# arduino-uno.net
KiCad netlist of a schematic drawn in Altium Designer
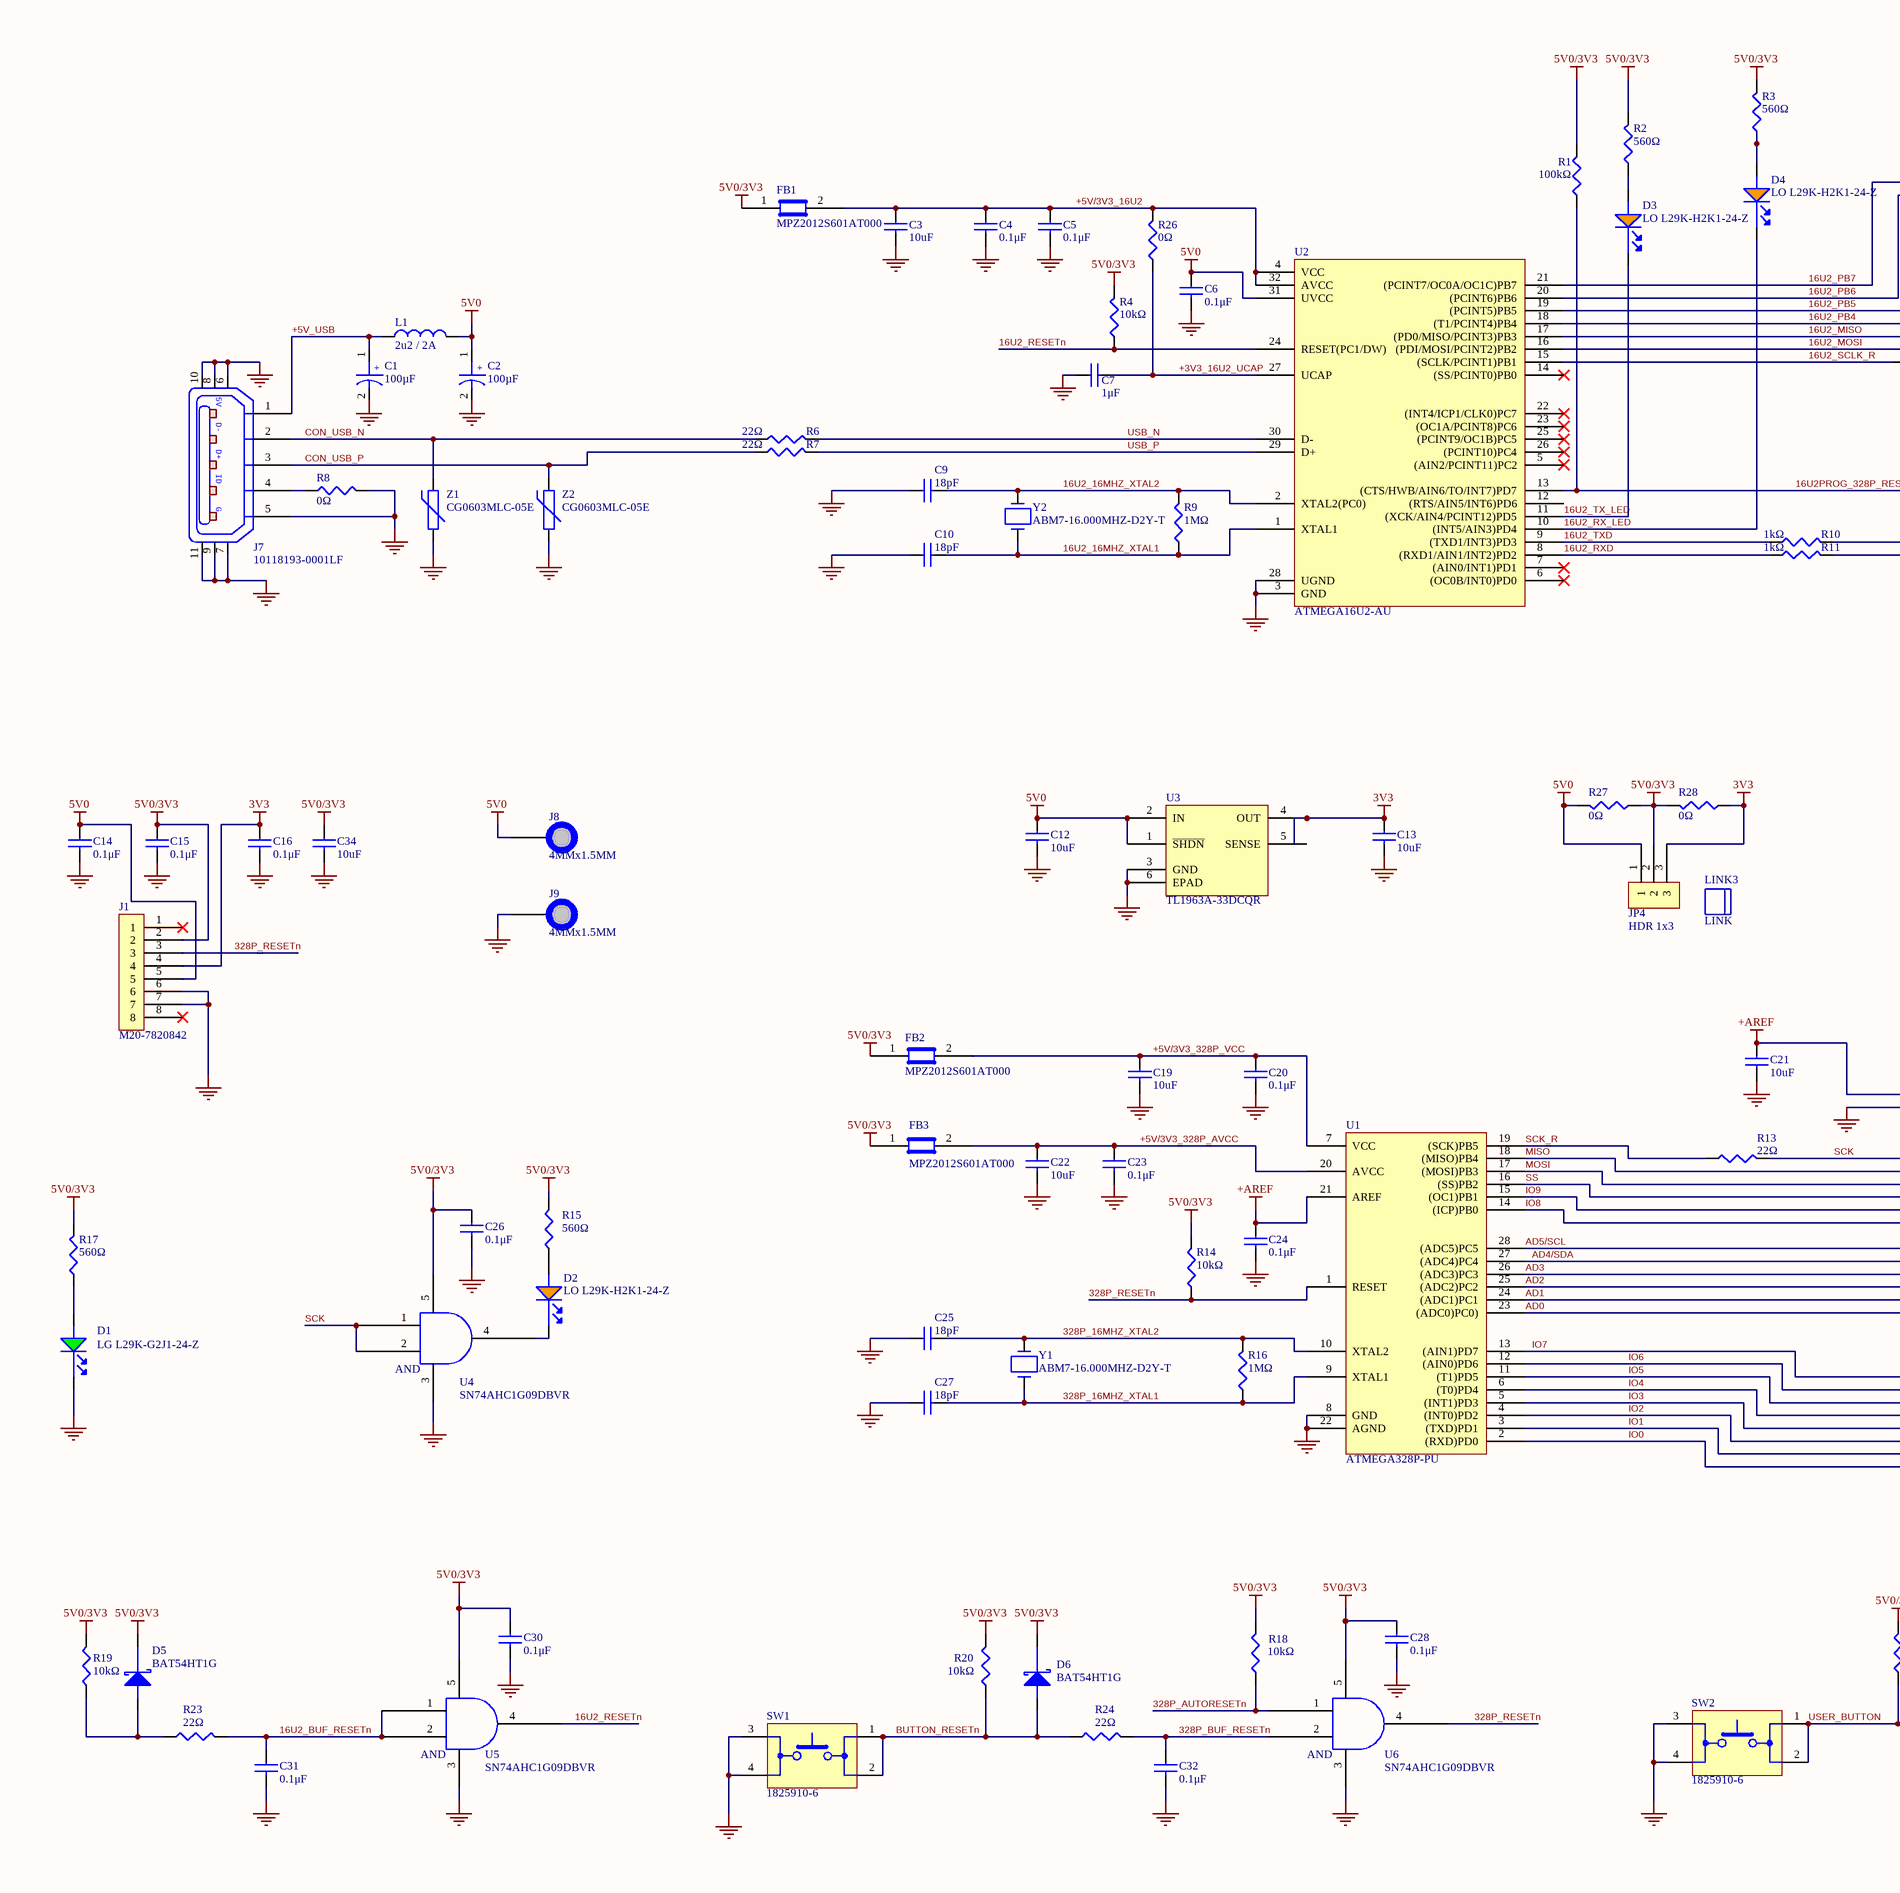
[diagram p0: arduino-uno.SchDoc, left]
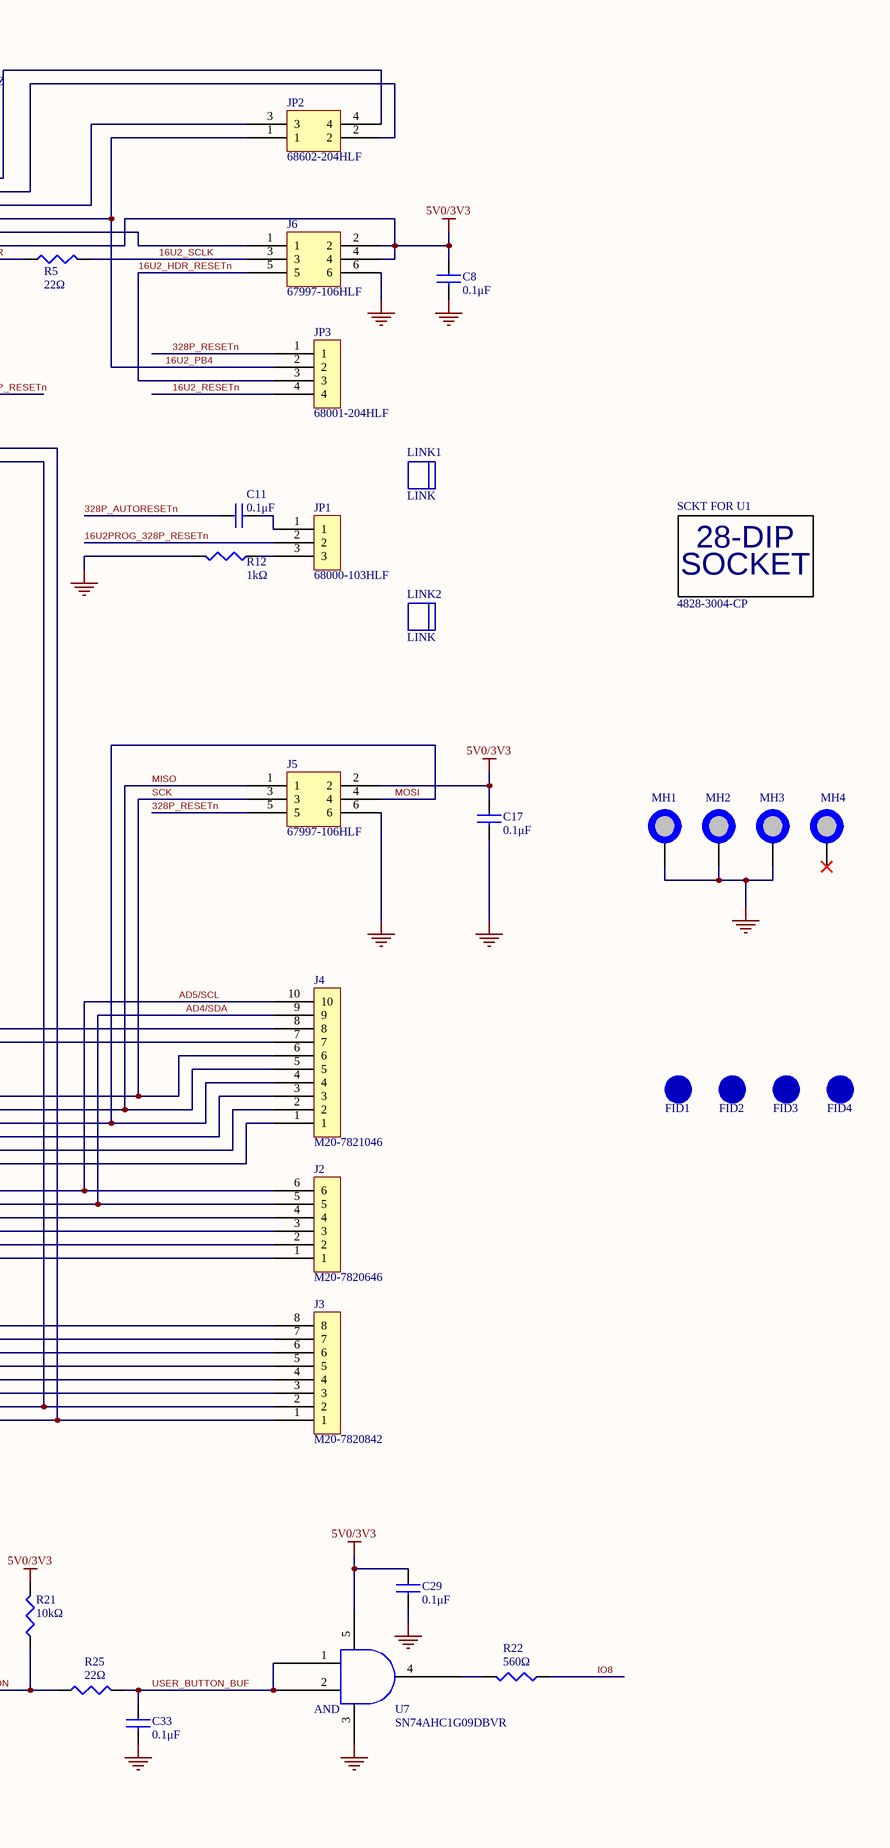
[diagram p1: arduino-uno.SchDoc, right]

(export (version "E")
  (design (tool "Eeschema 10.0.6"))
  (components
    (comp (ref "C1")
      (value "100µF")
      (footprint "C_ALU_C_SIZE")
      (description "CAP ALUM 100UF 10V 20% SMD")
      (fields
        (field (name "MANUFACTURER") "Panasonic Electronic Components")
        (field (name "MANUFACTURER PART NUMBER") "EEE-1AA101WR")
        (field (name ".CREATOR") "MM")
        (field (name ".CHECKED PCB") "RF")
        (field (name ".CHECKED SCH") "RF")
      )
      (libsource (lib "28Pins_Project_V1I1_PCB") (part "EEE-1AA101WR"))
    )
    (comp (ref "C2")
      (value "100µF")
      (footprint "C_ALU_C_SIZE")
      (description "CAP ALUM 100UF 10V 20% SMD")
      (fields
        (field (name "MANUFACTURER") "Panasonic Electronic Components")
        (field (name "MANUFACTURER PART NUMBER") "EEE-1AA101WR")
        (field (name ".CREATOR") "MM")
        (field (name ".CHECKED PCB") "RF")
        (field (name ".CHECKED SCH") "RF")
      )
      (libsource (lib "28Pins_Project_V1I1_PCB") (part "EEE-1AA101WR"))
    )
    (comp (ref "C3")
      (value "10uF")
      (footprint "C0805")
      (description "CAP CER 10UF 16V 20% X5R 0805")
      (fields
        (field (name "MANUFACTURER") "TDK Corporation")
        (field (name "MANUFACTURER PART NUMBER") "C2012X5R1C106M/1.25")
      )
      (libsource (lib "28Pins_Project_V1I1_PCB") (part "C2012X5R1C106M"))
    )
    (comp (ref "C4")
      (value "0.1μF")
      (footprint "C0805")
      (description "CAP CER 0.1UF 50V 10% X7R 0805")
      (fields
        (field (name "MANUFACTURER") "TDK Corporation")
        (field (name "MANUFACTURER PART NUMBER") "C2012X7R1H104K085AA")
        (field (name ".CREATOR") "MM")
        (field (name ".CHECKED PCB") "RF")
        (field (name ".CHECKED SCH") "RF")
      )
      (libsource (lib "28Pins_Project_V1I1_PCB") (part "C2012X7R1H104K085AA"))
    )
    (comp (ref "C5")
      (value "0.1μF")
      (footprint "C0805")
      (description "CAP CER 0.1UF 50V 10% X7R 0805")
      (fields
        (field (name "MANUFACTURER") "TDK Corporation")
        (field (name "MANUFACTURER PART NUMBER") "C2012X7R1H104K085AA")
        (field (name ".CREATOR") "MM")
        (field (name ".CHECKED PCB") "RF")
        (field (name ".CHECKED SCH") "RF")
      )
      (libsource (lib "28Pins_Project_V1I1_PCB") (part "C2012X7R1H104K085AA"))
    )
    (comp (ref "C6")
      (value "0.1μF")
      (footprint "C0805")
      (description "CAP CER 0.1UF 50V 10% X7R 0805")
      (fields
        (field (name "MANUFACTURER") "TDK Corporation")
        (field (name "MANUFACTURER PART NUMBER") "C2012X7R1H104K085AA")
        (field (name ".CREATOR") "MM")
        (field (name ".CHECKED PCB") "RF")
        (field (name ".CHECKED SCH") "RF")
      )
      (libsource (lib "28Pins_Project_V1I1_PCB") (part "C2012X7R1H104K085AA"))
    )
    (comp (ref "C7")
      (value "1μF")
      (footprint "C0805")
      (description "CAP CER 1UF 25V 10% X5R 0805")
      (fields
        (field (name "MANUFACTURER") "TDK Corporation")
        (field (name "MANUFACTURER PART NUMBER") "C2012X5R1E105K125AA")
        (field (name ".CREATOR") "MM")
        (field (name ".CHECKED PCB") "RF")
        (field (name ".CHECKED SCH") "RF")
      )
      (libsource (lib "28Pins_Project_V1I1_PCB") (part "C2012X5R1E105K125AA"))
    )
    (comp (ref "C8")
      (value "0.1μF")
      (footprint "C0805")
      (description "CAP CER 0.1UF 50V 10% X7R 0805")
      (fields
        (field (name "MANUFACTURER") "TDK Corporation")
        (field (name "MANUFACTURER PART NUMBER") "C2012X7R1H104K085AA")
        (field (name ".CREATOR") "MM")
        (field (name ".CHECKED PCB") "RF")
        (field (name ".CHECKED SCH") "RF")
      )
      (libsource (lib "28Pins_Project_V1I1_PCB") (part "C2012X7R1H104K085AA"))
    )
    (comp (ref "C9")
      (value "18pF")
      (footprint "C0805")
      (description "CAP CER 18PF 50V 5% NP0 0805")
      (fields
        (field (name "MANUFACTURER") "Kemet")
        (field (name "MANUFACTURER PART NUMBER") "C0805C180J5GACTU")
        (field (name ".CREATOR") "MM")
        (field (name ".CHECKED PCB") "RF")
        (field (name ".CHECKED SCH") "RF")
      )
      (libsource (lib "28Pins_Project_V1I1_PCB") (part "C0805C180J5GACTU"))
    )
    (comp (ref "C10")
      (value "18pF")
      (footprint "C0805")
      (description "CAP CER 18PF 50V 5% NP0 0805")
      (fields
        (field (name "MANUFACTURER") "Kemet")
        (field (name "MANUFACTURER PART NUMBER") "C0805C180J5GACTU")
        (field (name ".CREATOR") "MM")
        (field (name ".CHECKED PCB") "RF")
        (field (name ".CHECKED SCH") "RF")
      )
      (libsource (lib "28Pins_Project_V1I1_PCB") (part "C0805C180J5GACTU"))
    )
    (comp (ref "C11")
      (value "0.1μF")
      (footprint "C0805")
      (description "CAP CER 0.1UF 50V 10% X7R 0805")
      (fields
        (field (name "MANUFACTURER") "TDK Corporation")
        (field (name "MANUFACTURER PART NUMBER") "C2012X7R1H104K085AA")
        (field (name ".CREATOR") "MM")
        (field (name ".CHECKED PCB") "RF")
        (field (name ".CHECKED SCH") "RF")
      )
      (libsource (lib "28Pins_Project_V1I1_PCB") (part "C2012X7R1H104K085AA"))
    )
    (comp (ref "C12")
      (value "10uF")
      (footprint "C0805")
      (description "CAP CER 10UF 16V 20% X5R 0805")
      (fields
        (field (name "MANUFACTURER") "TDK Corporation")
        (field (name "MANUFACTURER PART NUMBER") "C2012X5R1C106M/1.25")
      )
      (libsource (lib "28Pins_Project_V1I1_PCB") (part "C2012X5R1C106M"))
    )
    (comp (ref "C13")
      (value "10uF")
      (footprint "C0805")
      (description "CAP CER 10UF 16V 20% X5R 0805")
      (fields
        (field (name "MANUFACTURER") "TDK Corporation")
        (field (name "MANUFACTURER PART NUMBER") "C2012X5R1C106M/1.25")
      )
      (libsource (lib "28Pins_Project_V1I1_PCB") (part "C2012X5R1C106M"))
    )
    (comp (ref "C14")
      (value "0.1μF")
      (footprint "C0805")
      (description "CAP CER 0.1UF 50V 10% X7R 0805")
      (fields
        (field (name "MANUFACTURER") "TDK Corporation")
        (field (name "MANUFACTURER PART NUMBER") "C2012X7R1H104K085AA")
        (field (name ".CREATOR") "MM")
        (field (name ".CHECKED PCB") "RF")
        (field (name ".CHECKED SCH") "RF")
      )
      (libsource (lib "28Pins_Project_V1I1_PCB") (part "C2012X7R1H104K085AA"))
    )
    (comp (ref "C15")
      (value "0.1μF")
      (footprint "C0805")
      (description "CAP CER 0.1UF 50V 10% X7R 0805")
      (fields
        (field (name "MANUFACTURER") "TDK Corporation")
        (field (name "MANUFACTURER PART NUMBER") "C2012X7R1H104K085AA")
        (field (name ".CREATOR") "MM")
        (field (name ".CHECKED PCB") "RF")
        (field (name ".CHECKED SCH") "RF")
      )
      (libsource (lib "28Pins_Project_V1I1_PCB") (part "C2012X7R1H104K085AA"))
    )
    (comp (ref "C16")
      (value "0.1μF")
      (footprint "C0805")
      (description "CAP CER 0.1UF 50V 10% X7R 0805")
      (fields
        (field (name "MANUFACTURER") "TDK Corporation")
        (field (name "MANUFACTURER PART NUMBER") "C2012X7R1H104K085AA")
        (field (name ".CREATOR") "MM")
        (field (name ".CHECKED PCB") "RF")
        (field (name ".CHECKED SCH") "RF")
      )
      (libsource (lib "28Pins_Project_V1I1_PCB") (part "C2012X7R1H104K085AA"))
    )
    (comp (ref "C17")
      (value "0.1μF")
      (footprint "C0805")
      (description "CAP CER 0.1UF 50V 10% X7R 0805")
      (fields
        (field (name "MANUFACTURER") "TDK Corporation")
        (field (name "MANUFACTURER PART NUMBER") "C2012X7R1H104K085AA")
        (field (name ".CREATOR") "MM")
        (field (name ".CHECKED PCB") "RF")
        (field (name ".CHECKED SCH") "RF")
      )
      (libsource (lib "28Pins_Project_V1I1_PCB") (part "C2012X7R1H104K085AA"))
    )
    (comp (ref "C19")
      (value "10uF")
      (footprint "C0805")
      (description "CAP CER 10UF 16V 20% X5R 0805")
      (fields
        (field (name "MANUFACTURER") "TDK Corporation")
        (field (name "MANUFACTURER PART NUMBER") "C2012X5R1C106M/1.25")
      )
      (libsource (lib "28Pins_Project_V1I1_PCB") (part "C2012X5R1C106M"))
    )
    (comp (ref "C20")
      (value "0.1μF")
      (footprint "C0805")
      (description "CAP CER 0.1UF 50V 10% X7R 0805")
      (fields
        (field (name "MANUFACTURER") "TDK Corporation")
        (field (name "MANUFACTURER PART NUMBER") "C2012X7R1H104K085AA")
        (field (name ".CREATOR") "MM")
        (field (name ".CHECKED PCB") "RF")
        (field (name ".CHECKED SCH") "RF")
      )
      (libsource (lib "28Pins_Project_V1I1_PCB") (part "C2012X7R1H104K085AA"))
    )
    (comp (ref "C21")
      (value "10uF")
      (footprint "C0805")
      (description "CAP CER 10UF 16V 20% X5R 0805")
      (fields
        (field (name "MANUFACTURER") "TDK Corporation")
        (field (name "MANUFACTURER PART NUMBER") "C2012X5R1C106M/1.25")
      )
      (libsource (lib "28Pins_Project_V1I1_PCB") (part "C2012X5R1C106M"))
    )
    (comp (ref "C22")
      (value "10uF")
      (footprint "C0805")
      (description "CAP CER 10UF 16V 20% X5R 0805")
      (fields
        (field (name "MANUFACTURER") "TDK Corporation")
        (field (name "MANUFACTURER PART NUMBER") "C2012X5R1C106M/1.25")
      )
      (libsource (lib "28Pins_Project_V1I1_PCB") (part "C2012X5R1C106M"))
    )
    (comp (ref "C23")
      (value "0.1μF")
      (footprint "C0805")
      (description "CAP CER 0.1UF 50V 10% X7R 0805")
      (fields
        (field (name "MANUFACTURER") "TDK Corporation")
        (field (name "MANUFACTURER PART NUMBER") "C2012X7R1H104K085AA")
        (field (name ".CREATOR") "MM")
        (field (name ".CHECKED PCB") "RF")
        (field (name ".CHECKED SCH") "RF")
      )
      (libsource (lib "28Pins_Project_V1I1_PCB") (part "C2012X7R1H104K085AA"))
    )
    (comp (ref "C24")
      (value "0.1μF")
      (footprint "C0805")
      (description "CAP CER 0.1UF 50V 10% X7R 0805")
      (fields
        (field (name "MANUFACTURER") "TDK Corporation")
        (field (name "MANUFACTURER PART NUMBER") "C2012X7R1H104K085AA")
        (field (name ".CREATOR") "MM")
        (field (name ".CHECKED PCB") "RF")
        (field (name ".CHECKED SCH") "RF")
      )
      (libsource (lib "28Pins_Project_V1I1_PCB") (part "C2012X7R1H104K085AA"))
    )
    (comp (ref "C25")
      (value "18pF")
      (footprint "C0805")
      (description "CAP CER 18PF 50V 5% NP0 0805")
      (fields
        (field (name "MANUFACTURER") "Kemet")
        (field (name "MANUFACTURER PART NUMBER") "C0805C180J5GACTU")
        (field (name ".CREATOR") "MM")
        (field (name ".CHECKED PCB") "RF")
        (field (name ".CHECKED SCH") "RF")
      )
      (libsource (lib "28Pins_Project_V1I1_PCB") (part "C0805C180J5GACTU"))
    )
    (comp (ref "C26")
      (value "0.1μF")
      (footprint "C0805")
      (description "CAP CER 0.1UF 50V 10% X7R 0805")
      (fields
        (field (name "MANUFACTURER") "TDK Corporation")
        (field (name "MANUFACTURER PART NUMBER") "C2012X7R1H104K085AA")
        (field (name ".CREATOR") "MM")
        (field (name ".CHECKED PCB") "RF")
        (field (name ".CHECKED SCH") "RF")
      )
      (libsource (lib "28Pins_Project_V1I1_PCB") (part "C2012X7R1H104K085AA"))
    )
    (comp (ref "C27")
      (value "18pF")
      (footprint "C0805")
      (description "CAP CER 18PF 50V 5% NP0 0805")
      (fields
        (field (name "MANUFACTURER") "Kemet")
        (field (name "MANUFACTURER PART NUMBER") "C0805C180J5GACTU")
        (field (name ".CREATOR") "MM")
        (field (name ".CHECKED PCB") "RF")
        (field (name ".CHECKED SCH") "RF")
      )
      (libsource (lib "28Pins_Project_V1I1_PCB") (part "C0805C180J5GACTU"))
    )
    (comp (ref "C28")
      (value "0.1μF")
      (footprint "C0805")
      (description "CAP CER 0.1UF 50V 10% X7R 0805")
      (fields
        (field (name "MANUFACTURER") "TDK Corporation")
        (field (name "MANUFACTURER PART NUMBER") "C2012X7R1H104K085AA")
        (field (name ".CREATOR") "MM")
        (field (name ".CHECKED PCB") "RF")
        (field (name ".CHECKED SCH") "RF")
      )
      (libsource (lib "28Pins_Project_V1I1_PCB") (part "C2012X7R1H104K085AA"))
    )
    (comp (ref "C29")
      (value "0.1μF")
      (footprint "C0805")
      (description "CAP CER 0.1UF 50V 10% X7R 0805")
      (fields
        (field (name "MANUFACTURER") "TDK Corporation")
        (field (name "MANUFACTURER PART NUMBER") "C2012X7R1H104K085AA")
        (field (name ".CREATOR") "MM")
        (field (name ".CHECKED PCB") "RF")
        (field (name ".CHECKED SCH") "RF")
      )
      (libsource (lib "28Pins_Project_V1I1_PCB") (part "C2012X7R1H104K085AA"))
    )
    (comp (ref "C30")
      (value "0.1μF")
      (footprint "C0805")
      (description "CAP CER 0.1UF 50V 10% X7R 0805")
      (fields
        (field (name "MANUFACTURER") "TDK Corporation")
        (field (name "MANUFACTURER PART NUMBER") "C2012X7R1H104K085AA")
        (field (name ".CREATOR") "MM")
        (field (name ".CHECKED PCB") "RF")
        (field (name ".CHECKED SCH") "RF")
      )
      (libsource (lib "28Pins_Project_V1I1_PCB") (part "C2012X7R1H104K085AA"))
    )
    (comp (ref "C31")
      (value "0.1μF")
      (footprint "C0805")
      (description "CAP CER 0.1UF 50V 10% X7R 0805")
      (fields
        (field (name "MANUFACTURER") "TDK Corporation")
        (field (name "MANUFACTURER PART NUMBER") "C2012X7R1H104K085AA")
        (field (name ".CREATOR") "MM")
        (field (name ".CHECKED PCB") "RF")
        (field (name ".CHECKED SCH") "RF")
      )
      (libsource (lib "28Pins_Project_V1I1_PCB") (part "C2012X7R1H104K085AA"))
    )
    (comp (ref "C32")
      (value "0.1μF")
      (footprint "C0805")
      (description "CAP CER 0.1UF 50V 10% X7R 0805")
      (fields
        (field (name "MANUFACTURER") "TDK Corporation")
        (field (name "MANUFACTURER PART NUMBER") "C2012X7R1H104K085AA")
        (field (name ".CREATOR") "MM")
        (field (name ".CHECKED PCB") "RF")
        (field (name ".CHECKED SCH") "RF")
      )
      (libsource (lib "28Pins_Project_V1I1_PCB") (part "C2012X7R1H104K085AA"))
    )
    (comp (ref "C33")
      (value "0.1μF")
      (footprint "C0805")
      (description "CAP CER 0.1UF 50V 10% X7R 0805")
      (fields
        (field (name "MANUFACTURER") "TDK Corporation")
        (field (name "MANUFACTURER PART NUMBER") "C2012X7R1H104K085AA")
        (field (name ".CREATOR") "MM")
        (field (name ".CHECKED PCB") "RF")
        (field (name ".CHECKED SCH") "RF")
      )
      (libsource (lib "28Pins_Project_V1I1_PCB") (part "C2012X7R1H104K085AA"))
    )
    (comp (ref "C34")
      (value "10uF")
      (footprint "C0805")
      (description "CAP CER 10UF 16V 20% X5R 0805")
      (fields
        (field (name "MANUFACTURER") "TDK Corporation")
        (field (name "MANUFACTURER PART NUMBER") "C2012X5R1C106M/1.25")
      )
      (libsource (lib "28Pins_Project_V1I1_PCB") (part "C2012X5R1C106M"))
    )
    (comp (ref "D1")
      (value "LG L29K-G2J1-24-Z")
      (footprint "LED_0603")
      (description "LED SMARTLED GREEN 570NM 0603")
      (fields (field (name "MANUFACTURER") "OSRAM Opto Semiconductors Inc"))
      (libsource (lib "28Pins_Project_V1I1_PCB") (part "LG L29K-G2J1-24-Z"))
    )
    (comp (ref "D2")
      (value "LO L29K-H2K1-24-Z")
      (footprint "LED_0603")
      (description "LED SMARTLED ORANGE 606NM 0603")
      (fields (field (name "MANUFACTURER") "OSRAM Opto Semiconductors Inc"))
      (libsource (lib "28Pins_Project_V1I1_PCB") (part "LO L29K-H2K1-24-Z"))
    )
    (comp (ref "D3")
      (value "LO L29K-H2K1-24-Z")
      (footprint "LED_0603")
      (description "LED SMARTLED ORANGE 606NM 0603")
      (fields (field (name "MANUFACTURER") "OSRAM Opto Semiconductors Inc"))
      (libsource (lib "28Pins_Project_V1I1_PCB") (part "LO L29K-H2K1-24-Z"))
    )
    (comp (ref "D4")
      (value "LO L29K-H2K1-24-Z")
      (footprint "LED_0603")
      (description "LED SMARTLED ORANGE 606NM 0603")
      (fields (field (name "MANUFACTURER") "OSRAM Opto Semiconductors Inc"))
      (libsource (lib "28Pins_Project_V1I1_PCB") (part "LO L29K-H2K1-24-Z"))
    )
    (comp (ref "D5")
      (value "BAT54HT1G")
      (footprint "SOD323")
      (description "DIODE SCHOTTKY 30V 0.2A SOD323")
      (fields (field (name "MANUFACTURER") "Fairchild Semiconductor") (field (name ".CREATOR") "MM"))
      (libsource (lib "28Pins_Project_V1I1_PCB") (part "BAT54HT1G"))
    )
    (comp (ref "D6")
      (value "BAT54HT1G")
      (footprint "SOD323")
      (description "DIODE SCHOTTKY 30V 0.2A SOD323")
      (fields (field (name "MANUFACTURER") "Fairchild Semiconductor") (field (name ".CREATOR") "MM"))
      (libsource (lib "28Pins_Project_V1I1_PCB") (part "BAT54HT1G"))
    )
    (comp (ref "FB1")
      (value "MPZ2012S601AT000")
      (footprint "C0805")
      (description "FERRITE CHIP BEAD 600 OHM SMD")
      (fields
        (field (name "MANUFACTURER") "TDK Corporation")
        (field (name ".CREATOR") "MM")
        (field (name ".CHECKED PCB") "RF")
        (field (name ".CHECKED SCH") "RF")
      )
      (libsource (lib "28Pins_Project_V1I1_PCB") (part "MPZ2012S601AT000"))
    )
    (comp (ref "FB2")
      (value "MPZ2012S601AT000")
      (footprint "C0805")
      (description "FERRITE CHIP BEAD 600 OHM SMD")
      (fields
        (field (name "MANUFACTURER") "TDK Corporation")
        (field (name ".CREATOR") "MM")
        (field (name ".CHECKED PCB") "RF")
        (field (name ".CHECKED SCH") "RF")
      )
      (libsource (lib "28Pins_Project_V1I1_PCB") (part "MPZ2012S601AT000"))
    )
    (comp (ref "FB3")
      (value "MPZ2012S601AT000")
      (footprint "C0805")
      (description "FERRITE CHIP BEAD 600 OHM SMD")
      (fields
        (field (name "MANUFACTURER") "TDK Corporation")
        (field (name ".CREATOR") "MM")
        (field (name ".CHECKED PCB") "RF")
        (field (name ".CHECKED SCH") "RF")
      )
      (libsource (lib "28Pins_Project_V1I1_PCB") (part "MPZ2012S601AT000"))
    )
    (comp (ref "FID1")
      (value "FID_1MMC")
      (footprint "FID_40X120D")
      (description "Fiducial 40mil Diameter, 120mil Mask")
      (libsource (lib "28Pins_Project_V1I1_PCB") (part "FID_1MMC"))
    )
    (comp (ref "FID2")
      (value "FID_1MMC")
      (footprint "FID_40X120D")
      (description "Fiducial 40mil Diameter, 120mil Mask")
      (libsource (lib "28Pins_Project_V1I1_PCB") (part "FID_1MMC"))
    )
    (comp (ref "FID3")
      (value "FID_1MMC")
      (footprint "FID_40X120D")
      (description "Fiducial 40mil Diameter, 120mil Mask")
      (libsource (lib "28Pins_Project_V1I1_PCB") (part "FID_1MMC"))
    )
    (comp (ref "FID4")
      (value "FID_1MMC")
      (footprint "FID_40X120D")
      (description "Fiducial 40mil Diameter, 120mil Mask")
      (libsource (lib "28Pins_Project_V1I1_PCB") (part "FID_1MMC"))
    )
    (comp (ref "J1")
      (value "M20-7820842")
      (footprint "Hdr_Female_1x8_2.54mm")
      (description "08-WAY SIL VERT SOCKET L/FREE")
      (fields
        (field (name "MANUFACTURER") "Harwin Inc")
        (field (name ".CREATOR") "MM")
        (field (name ".CHECKED PCB") "RF")
        (field (name ".CHECKED SCH") "RF")
      )
      (libsource (lib "") (part "M20-7820842_1"))
    )
    (comp (ref "J2")
      (value "M20-7820646")
      (footprint "Hdr_Female_1x6_2.54mm")
      (description "06-WAY SIL VERT SOCKET L/FREE")
      (fields
        (field (name "MANUFACTURER") "Harwin Inc")
        (field (name ".CHECKED PCB") "MM")
        (field (name ".CHECKED SCH") "MM")
        (field (name ".CREATOR") "MM")
      )
      (libsource (lib "28Pins_Project_V1I1_PCB") (part "M20-7820646"))
    )
    (comp (ref "J3")
      (value "M20-7820842")
      (footprint "Hdr_Female_1x8_2.54mm")
      (description "08-WAY SIL VERT SOCKET L/FREE")
      (fields
        (field (name "MANUFACTURER") "Harwin Inc")
        (field (name ".CREATOR") "MM")
        (field (name ".CHECKED PCB") "RF")
        (field (name ".CHECKED SCH") "RF")
      )
      (libsource (lib "28Pins_Project_V1I1_PCB") (part "M20-7820842"))
    )
    (comp (ref "J4")
      (value "M20-7821046")
      (footprint "Hdr_Female_1x10_2.54mm")
      (description "10-WAY SIL VERT SOCKET L/FREE")
      (fields
        (field (name "MANUFACTURER") "Harwin Inc")
        (field (name ".CREATOR") "MM")
        (field (name ".CHECKED PCB") "RF")
        (field (name ".CHECKED SCH") "RF")
      )
      (libsource (lib "28Pins_Project_V1I1_PCB") (part "M20-7821046"))
    )
    (comp (ref "J5")
      (value "67997-106HLF")
      (footprint "HDR_2x3_2.54MM")
      (description "CONN HEADER 6POS .100 STR 30AU")
      (fields
        (field (name "MANUFACTURER") "FCI")
        (field (name ".CREATOR") "MM")
        (field (name ".CHECKED PCB") "RF")
        (field (name ".CHECKED SCH") "RF")
      )
      (libsource (lib "28Pins_Project_V1I1_PCB") (part "67997-106HLF"))
    )
    (comp (ref "J6")
      (value "67997-106HLF")
      (footprint "HDR_2x3_2.54MM")
      (description "CONN HEADER 6POS .100 STR 30AU")
      (fields
        (field (name "MANUFACTURER") "FCI")
        (field (name ".CREATOR") "MM")
        (field (name ".CHECKED PCB") "RF")
        (field (name ".CHECKED SCH") "RF")
      )
      (libsource (lib "28Pins_Project_V1I1_PCB") (part "67997-106HLF"))
    )
    (comp (ref "J7")
      (value "10118193-0001LF")
      (footprint "10118193")
      (description "CONN USB MICRO B RECPT SMT R/A")
      (fields
        (field (name "MANUFACTURER") "FCI")
        (field (name ".CREATOR") "MM")
        (field (name ".CHECKED PCB") "RF")
        (field (name ".CHECKED SCH") "MM")
      )
      (libsource (lib "28Pins_Project_V1I1_PCB") (part "10118193-0001LF"))
    )
    (comp (ref "J8")
      (value "4MMx1.5MM")
      (footprint "PAD_WITH_HOLE_4MMx1.5MM")
      (description "Pad with a hole 4mm x 1.5mm")
      (libsource (lib "28Pins_Project_V1I1_PCB") (part "PAD_WITH_HOLE_4MMx1.5MM"))
    )
    (comp (ref "J9")
      (value "4MMx1.5MM")
      (footprint "PAD_WITH_HOLE_4MMx1.5MM")
      (description "Pad with a hole 4mm x 1.5mm")
      (libsource (lib "28Pins_Project_V1I1_PCB") (part "PAD_WITH_HOLE_4MMx1.5MM"))
    )
    (comp (ref "JP1")
      (value "68000-103HLF")
      (footprint "Hdr_1x3_2.54mm")
      (description "BERGSTIK II .100\" SR STRAIGHT")
      (fields (field (name "MANUFACTURER") "FCI") (field (name ".CREATOR") "MM"))
      (libsource (lib "") (part "68000-103HLF_1"))
    )
    (comp (ref "JP2")
      (value "68602-204HLF")
      (footprint "HDR_2x2_2.54MM")
      (description "CONN HEADER 4POS .100 STR 15AU")
      (fields
        (field (name "MANUFACTURER") "FCI")
        (field (name ".CREATOR") "MM")
        (field (name ".CHECKED PCB") "RF")
        (field (name ".CHECKED SCH") "RF")
      )
      (libsource (lib "28Pins_Project_V1I1_PCB") (part "68602-204HLF"))
    )
    (comp (ref "JP3")
      (value "68001-204HLF")
      (footprint "HDR_1x4_2.54MM")
      (description "CONN HEADER 4POS .100 STR 15AU")
      (fields
        (field (name "MANUFACTURER") "FCI")
        (field (name ".CHECKED PCB") "RF")
        (field (name ".CHECKED SCH") "RF")
      )
      (libsource (lib "28Pins_Project_V1I1_PCB") (part "68001-204HLF"))
    )
    (comp (ref "JP4")
      (value "HDR 1x3")
      (footprint "Hdr_1x3_2.54mm")
      (description "BERGSTIK II .100\" SR STRAIGHT")
      (fields
        (field (name "MANUFACTURER") "FCI")
        (field (name "MANUFACTURER PART NUMBER") "68000-103HLF")
        (field (name ".CREATOR") "MM")
      )
      (libsource (lib "28Pins_Project_V1I1_PCB") (part "68000-103HLF"))
    )
    (comp (ref "L1")
      (value "2u2 / 2A")
      (footprint "C1210_IND")
      (description "FIXED IND 2.2UH 2A 80 MOHM SMD")
      (fields
        (field (name "MANUFACTURER") "Kemet")
        (field (name "MANUFACTURER PART NUMBER") "L1210R2R2MDWIT")
        (field (name ".CREATOR") "MM")
        (field (name ".CHECKED PCB") "RF")
        (field (name ".CHECKED SCH") "RF")
      )
      (libsource (lib "28Pins_Project_V1I1_PCB") (part "L1210R2R2MDWIT"))
    )
    (comp (ref "LINK1")
      (value "LINK")
      (description "CONN JUMPER SHORTING .100\" GOLD")
      (fields
        (field (name "MANUFACTURER") "Sullins Connector Solutions")
        (field (name "MANUFACTURER PART NUMBER") "QPC02SXGN-RC")
      )
      (libsource (lib "28Pins_Project_V1I1_PCB") (part "QPC02SXGN-RC"))
    )
    (comp (ref "LINK2")
      (value "LINK")
      (description "CONN JUMPER SHORTING .100\" GOLD")
      (fields
        (field (name "MANUFACTURER") "Sullins Connector Solutions")
        (field (name "MANUFACTURER PART NUMBER") "QPC02SXGN-RC")
      )
      (libsource (lib "28Pins_Project_V1I1_PCB") (part "QPC02SXGN-RC"))
    )
    (comp (ref "LINK3")
      (value "LINK")
      (description "CONN JUMPER SHORTING .100\" GOLD")
      (fields
        (field (name "MANUFACTURER") "Sullins Connector Solutions")
        (field (name "MANUFACTURER PART NUMBER") "QPC02SXGN-RC")
      )
      (libsource (lib "28Pins_Project_V1I1_PCB") (part "QPC02SXGN-RC"))
    )
    (comp (ref "MH1")
      (value "MH_7.4MMC_3.2MMD")
      (footprint "MH_7.4MMD_3.2MMD")
      (description "Mounting Hole 7.4mm Diameter, 3.2mm Drill")
      (fields (field (name ".CREATOR") "MM"))
      (libsource (lib "28Pins_Project_V1I1_PCB") (part "MH_7.4MMC_3.2MMD"))
    )
    (comp (ref "MH2")
      (value "MH_7.4MMC_3.2MMD")
      (footprint "MH_7.4MMD_3.2MMD")
      (description "Mounting Hole 7.4mm Diameter, 3.2mm Drill")
      (fields (field (name ".CREATOR") "MM"))
      (libsource (lib "28Pins_Project_V1I1_PCB") (part "MH_7.4MMC_3.2MMD"))
    )
    (comp (ref "MH3")
      (value "MH_7.4MMC_3.2MMD")
      (footprint "MH_7.4MMD_3.2MMD")
      (description "Mounting Hole 7.4mm Diameter, 3.2mm Drill")
      (fields (field (name ".CREATOR") "MM"))
      (libsource (lib "28Pins_Project_V1I1_PCB") (part "MH_7.4MMC_3.2MMD"))
    )
    (comp (ref "MH4")
      (value "MH_7.4MMNC_3.2MMD")
      (footprint "MH_7.4MMD_3.2MMD_NON_COPPER_NPTH")
      (description "Mounting Hole 7.4mm Diameter (Non Copper), 3.2mm Drill NPTH")
      (libsource (lib "28Pins_Project_V1I1_PCB") (part "MH_7.4MMNC_3.2MMD"))
    )
    (comp (ref "R1")
      (value "100kΩ")
      (footprint "R0805")
      (description "RES SMD 100K OHM 1% 1/8W 0805")
      (fields
        (field (name "MANUFACTURER") "Yageo")
        (field (name "MANUFACTURER PART NUMBER") "RC0805FR-07100KL")
        (field (name ".CREATOR") "MM")
        (field (name ".CHECKED PCB") "RF")
        (field (name ".CHECKED SCH") "RF")
      )
      (libsource (lib "28Pins_Project_V1I1_PCB") (part "RC0805FR-07100KL"))
    )
    (comp (ref "R2")
      (value "560Ω")
      (footprint "R0805")
      (description "RES SMD 560 OHM 1% 1/8W 0805")
      (fields
        (field (name "MANUFACTURER") "Yageo")
        (field (name "MANUFACTURER PART NUMBER") "RC0805FR-07560RL")
        (field (name ".CREATOR") "MM")
        (field (name ".CHECKED PCB") "RF")
        (field (name ".CHECKED SCH") "RF")
      )
      (libsource (lib "28Pins_Project_V1I1_PCB") (part "RC0805FR-07560RL"))
    )
    (comp (ref "R3")
      (value "560Ω")
      (footprint "R0805")
      (description "RES SMD 560 OHM 1% 1/8W 0805")
      (fields
        (field (name "MANUFACTURER") "Yageo")
        (field (name "MANUFACTURER PART NUMBER") "RC0805FR-07560RL")
        (field (name ".CREATOR") "MM")
        (field (name ".CHECKED PCB") "RF")
        (field (name ".CHECKED SCH") "RF")
      )
      (libsource (lib "28Pins_Project_V1I1_PCB") (part "RC0805FR-07560RL"))
    )
    (comp (ref "R4")
      (value "10kΩ")
      (footprint "R0805")
      (description "RES SMD 10K OHM 1% 1/8W 0805")
      (fields
        (field (name "MANUFACTURER") "Yageo")
        (field (name "MANUFACTURER PART NUMBER") "RC0805FR-0710KL")
        (field (name ".CREATOR") "MM")
        (field (name ".CHECKED PCB") "RF")
        (field (name ".CHECKED SCH") "RF")
      )
      (libsource (lib "28Pins_Project_V1I1_PCB") (part "RC0805FR-0710KL"))
    )
    (comp (ref "R5")
      (value "22Ω")
      (footprint "R0805")
      (description "RES SMD 22 OHM 1% 1/8W 0805")
      (fields
        (field (name "MANUFACTURER") "Yageo")
        (field (name "MANUFACTURER PART NUMBER") "RC0805FR-0722RL")
        (field (name ".CREATOR") "MM")
        (field (name ".CHECKED PCB") "RF")
        (field (name ".CHECKED SCH") "RF")
      )
      (libsource (lib "28Pins_Project_V1I1_PCB") (part "RC0805FR-0722RL"))
    )
    (comp (ref "R6")
      (value "22Ω")
      (footprint "R0805")
      (description "RES SMD 22 OHM 1% 1/8W 0805")
      (fields
        (field (name "MANUFACTURER") "Yageo")
        (field (name "MANUFACTURER PART NUMBER") "RC0805FR-0722RL")
        (field (name ".CREATOR") "MM")
        (field (name ".CHECKED PCB") "RF")
        (field (name ".CHECKED SCH") "RF")
      )
      (libsource (lib "28Pins_Project_V1I1_PCB") (part "RC0805FR-0722RL"))
    )
    (comp (ref "R7")
      (value "22Ω")
      (footprint "R0805")
      (description "RES SMD 22 OHM 1% 1/8W 0805")
      (fields
        (field (name "MANUFACTURER") "Yageo")
        (field (name "MANUFACTURER PART NUMBER") "RC0805FR-0722RL")
        (field (name ".CREATOR") "MM")
        (field (name ".CHECKED PCB") "RF")
        (field (name ".CHECKED SCH") "RF")
      )
      (libsource (lib "28Pins_Project_V1I1_PCB") (part "RC0805FR-0722RL"))
    )
    (comp (ref "R8")
      (value "0Ω")
      (footprint "R0805")
      (description "RES 0.0 OHM 1/8W 0805 SMD")
      (fields
        (field (name "MANUFACTURER") "Yageo")
        (field (name "MANUFACTURER PART NUMBER") "RC0805JR-070RL")
        (field (name ".CHECKED PCB") "RF")
        (field (name ".CHECKED SCH") "RF")
      )
      (libsource (lib "28Pins_Project_V1I1_PCB") (part "RC0805JR-070RL"))
    )
    (comp (ref "R9")
      (value "1MΩ")
      (footprint "R0805")
      (description "RES SMD 1M OHM 1% 1/8W 0805")
      (fields
        (field (name "MANUFACTURER") "Yageo")
        (field (name "MANUFACTURER PART NUMBER") "RC0805FR-071ML")
        (field (name ".CREATOR") "MM")
        (field (name ".CHECKED PCB") "RF")
        (field (name ".CHECKED SCH") "RF")
      )
      (libsource (lib "28Pins_Project_V1I1_PCB") (part "RC0805FR-071ML"))
    )
    (comp (ref "R10")
      (value "1kΩ")
      (footprint "R0805")
      (description "RES SMD 1K OHM 1% 1/8W 0805")
      (fields
        (field (name "MANUFACTURER") "Yageo")
        (field (name "MANUFACTURER PART NUMBER") "RC0805FR-071KL")
        (field (name ".CREATOR") "MM")
        (field (name ".CHECKED PCB") "RF")
        (field (name ".CHECKED SCH") "RF")
      )
      (libsource (lib "28Pins_Project_V1I1_PCB") (part "RC0805FR-071KL"))
    )
    (comp (ref "R11")
      (value "1kΩ")
      (footprint "R0805")
      (description "RES SMD 1K OHM 1% 1/8W 0805")
      (fields
        (field (name "MANUFACTURER") "Yageo")
        (field (name "MANUFACTURER PART NUMBER") "RC0805FR-071KL")
        (field (name ".CREATOR") "MM")
        (field (name ".CHECKED PCB") "RF")
        (field (name ".CHECKED SCH") "RF")
      )
      (libsource (lib "28Pins_Project_V1I1_PCB") (part "RC0805FR-071KL"))
    )
    (comp (ref "R12")
      (value "1kΩ")
      (footprint "R0805")
      (description "RES SMD 1K OHM 1% 1/8W 0805")
      (fields
        (field (name "MANUFACTURER") "Yageo")
        (field (name "MANUFACTURER PART NUMBER") "RC0805FR-071KL")
        (field (name ".CREATOR") "MM")
        (field (name ".CHECKED PCB") "RF")
        (field (name ".CHECKED SCH") "RF")
      )
      (libsource (lib "28Pins_Project_V1I1_PCB") (part "RC0805FR-071KL"))
    )
    (comp (ref "R13")
      (value "22Ω")
      (footprint "R0805")
      (description "RES SMD 22 OHM 1% 1/8W 0805")
      (fields
        (field (name "MANUFACTURER") "Yageo")
        (field (name "MANUFACTURER PART NUMBER") "RC0805FR-0722RL")
        (field (name ".CREATOR") "MM")
        (field (name ".CHECKED PCB") "RF")
        (field (name ".CHECKED SCH") "RF")
      )
      (libsource (lib "28Pins_Project_V1I1_PCB") (part "RC0805FR-0722RL"))
    )
    (comp (ref "R14")
      (value "10kΩ")
      (footprint "R0805")
      (description "RES SMD 10K OHM 1% 1/8W 0805")
      (fields
        (field (name "MANUFACTURER") "Yageo")
        (field (name "MANUFACTURER PART NUMBER") "RC0805FR-0710KL")
        (field (name ".CREATOR") "MM")
        (field (name ".CHECKED PCB") "RF")
        (field (name ".CHECKED SCH") "RF")
      )
      (libsource (lib "28Pins_Project_V1I1_PCB") (part "RC0805FR-0710KL"))
    )
    (comp (ref "R15")
      (value "560Ω")
      (footprint "R0805")
      (description "RES SMD 560 OHM 1% 1/8W 0805")
      (fields
        (field (name "MANUFACTURER") "Yageo")
        (field (name "MANUFACTURER PART NUMBER") "RC0805FR-07560RL")
        (field (name ".CREATOR") "MM")
        (field (name ".CHECKED PCB") "RF")
        (field (name ".CHECKED SCH") "RF")
      )
      (libsource (lib "28Pins_Project_V1I1_PCB") (part "RC0805FR-07560RL"))
    )
    (comp (ref "R16")
      (value "1MΩ")
      (footprint "R0805")
      (description "RES SMD 1M OHM 1% 1/8W 0805")
      (fields
        (field (name "MANUFACTURER") "Yageo")
        (field (name "MANUFACTURER PART NUMBER") "RC0805FR-071ML")
        (field (name ".CREATOR") "MM")
        (field (name ".CHECKED PCB") "RF")
        (field (name ".CHECKED SCH") "RF")
      )
      (libsource (lib "28Pins_Project_V1I1_PCB") (part "RC0805FR-071ML"))
    )
    (comp (ref "R17")
      (value "560Ω")
      (footprint "R0805")
      (description "RES SMD 560 OHM 1% 1/8W 0805")
      (fields
        (field (name "MANUFACTURER") "Yageo")
        (field (name "MANUFACTURER PART NUMBER") "RC0805FR-07560RL")
        (field (name ".CREATOR") "MM")
        (field (name ".CHECKED PCB") "RF")
        (field (name ".CHECKED SCH") "RF")
      )
      (libsource (lib "28Pins_Project_V1I1_PCB") (part "RC0805FR-07560RL"))
    )
    (comp (ref "R18")
      (value "10kΩ")
      (footprint "R0805")
      (description "RES SMD 10K OHM 1% 1/8W 0805")
      (fields
        (field (name "MANUFACTURER") "Yageo")
        (field (name "MANUFACTURER PART NUMBER") "RC0805FR-0710KL")
        (field (name ".CREATOR") "MM")
        (field (name ".CHECKED PCB") "RF")
        (field (name ".CHECKED SCH") "RF")
      )
      (libsource (lib "28Pins_Project_V1I1_PCB") (part "RC0805FR-0710KL"))
    )
    (comp (ref "R19")
      (value "10kΩ")
      (footprint "R0805")
      (description "RES SMD 10K OHM 1% 1/8W 0805")
      (fields
        (field (name "MANUFACTURER") "Yageo")
        (field (name "MANUFACTURER PART NUMBER") "RC0805FR-0710KL")
        (field (name ".CREATOR") "MM")
        (field (name ".CHECKED PCB") "RF")
        (field (name ".CHECKED SCH") "RF")
      )
      (libsource (lib "28Pins_Project_V1I1_PCB") (part "RC0805FR-0710KL"))
    )
    (comp (ref "R20")
      (value "10kΩ")
      (footprint "R0805")
      (description "RES SMD 10K OHM 1% 1/8W 0805")
      (fields
        (field (name "MANUFACTURER") "Yageo")
        (field (name "MANUFACTURER PART NUMBER") "RC0805FR-0710KL")
        (field (name ".CREATOR") "MM")
        (field (name ".CHECKED PCB") "RF")
        (field (name ".CHECKED SCH") "RF")
      )
      (libsource (lib "28Pins_Project_V1I1_PCB") (part "RC0805FR-0710KL"))
    )
    (comp (ref "R21")
      (value "10kΩ")
      (footprint "R0805")
      (description "RES SMD 10K OHM 1% 1/8W 0805")
      (fields
        (field (name "MANUFACTURER") "Yageo")
        (field (name "MANUFACTURER PART NUMBER") "RC0805FR-0710KL")
        (field (name ".CREATOR") "MM")
        (field (name ".CHECKED PCB") "RF")
        (field (name ".CHECKED SCH") "RF")
      )
      (libsource (lib "28Pins_Project_V1I1_PCB") (part "RC0805FR-0710KL"))
    )
    (comp (ref "R22")
      (value "560Ω")
      (footprint "R0805")
      (description "RES SMD 560 OHM 1% 1/8W 0805")
      (fields
        (field (name "MANUFACTURER") "Yageo")
        (field (name "MANUFACTURER PART NUMBER") "RC0805FR-07560RL")
        (field (name ".CREATOR") "MM")
        (field (name ".CHECKED PCB") "RF")
        (field (name ".CHECKED SCH") "RF")
      )
      (libsource (lib "28Pins_Project_V1I1_PCB") (part "RC0805FR-07560RL"))
    )
    (comp (ref "R23")
      (value "22Ω")
      (footprint "R0805")
      (description "RES SMD 22 OHM 1% 1/8W 0805")
      (fields
        (field (name "MANUFACTURER") "Yageo")
        (field (name "MANUFACTURER PART NUMBER") "RC0805FR-0722RL")
        (field (name ".CREATOR") "MM")
        (field (name ".CHECKED PCB") "RF")
        (field (name ".CHECKED SCH") "RF")
      )
      (libsource (lib "28Pins_Project_V1I1_PCB") (part "RC0805FR-0722RL"))
    )
    (comp (ref "R24")
      (value "22Ω")
      (footprint "R0805")
      (description "RES SMD 22 OHM 1% 1/8W 0805")
      (fields
        (field (name "MANUFACTURER") "Yageo")
        (field (name "MANUFACTURER PART NUMBER") "RC0805FR-0722RL")
        (field (name ".CREATOR") "MM")
        (field (name ".CHECKED PCB") "RF")
        (field (name ".CHECKED SCH") "RF")
      )
      (libsource (lib "28Pins_Project_V1I1_PCB") (part "RC0805FR-0722RL"))
    )
    (comp (ref "R25")
      (value "22Ω")
      (footprint "R0805")
      (description "RES SMD 22 OHM 1% 1/8W 0805")
      (fields
        (field (name "MANUFACTURER") "Yageo")
        (field (name "MANUFACTURER PART NUMBER") "RC0805FR-0722RL")
        (field (name ".CREATOR") "MM")
        (field (name ".CHECKED PCB") "RF")
        (field (name ".CHECKED SCH") "RF")
      )
      (libsource (lib "28Pins_Project_V1I1_PCB") (part "RC0805FR-0722RL"))
    )
    (comp (ref "R26")
      (value "0Ω")
      (footprint "R0805")
      (description "RES 0.0 OHM 1/8W 0805 SMD")
      (fields
        (field (name "MANUFACTURER") "Yageo")
        (field (name "MANUFACTURER PART NUMBER") "RC0805JR-070RL")
        (field (name ".CHECKED PCB") "RF")
        (field (name ".CHECKED SCH") "RF")
      )
      (libsource (lib "28Pins_Project_V1I1_PCB") (part "RC0805JR-070RL"))
    )
    (comp (ref "R27")
      (value "0Ω")
      (footprint "R0805")
      (description "RES 0.0 OHM 1/8W 0805 SMD")
      (fields
        (field (name "MANUFACTURER") "Yageo")
        (field (name "MANUFACTURER PART NUMBER") "RC0805JR-070RL")
        (field (name ".CHECKED PCB") "RF")
        (field (name ".CHECKED SCH") "RF")
      )
      (libsource (lib "28Pins_Project_V1I1_PCB") (part "RC0805JR-070RL"))
    )
    (comp (ref "R28")
      (value "0Ω")
      (footprint "R0805")
      (description "RES 0.0 OHM 1/8W 0805 SMD")
      (fields
        (field (name "MANUFACTURER") "Yageo")
        (field (name "MANUFACTURER PART NUMBER") "RC0805JR-070RL")
        (field (name ".CHECKED PCB") "RF")
        (field (name ".CHECKED SCH") "RF")
      )
      (libsource (lib "28Pins_Project_V1I1_PCB") (part "RC0805JR-070RL"))
    )
    (comp (ref "SCKT FOR U1")
      (value "4828-3004-CP")
      (footprint "28_DIP_7.62mm_SOCKET")
      (description "CONN IC DIP SOCKET 28POS TIN")
      (fields
        (field (name "MANUFACTURER") "3M")
        (field (name ".CREATOR") "MM")
        (field (name ".CHECKED PCB") "RF")
        (field (name ".CHECKED SCH") "RF")
      )
      (libsource (lib "28Pins_Project_V1I1_PCB") (part "4828-3004-CP"))
    )
    (comp (ref "SW1")
      (value "1825910-6")
      (footprint "1825910-6")
      (description "SWITCH TACTILE SPST-NO 0.05A 24V")
      (fields
        (field (name "MANUFACTURER") "TE Connectivity")
        (field (name ".CREATOR") "MM")
        (field (name ".CHECKED PCB") "RF")
        (field (name ".CHECKED SCH") "RF")
      )
      (libsource (lib "28Pins_Project_V1I1_PCB") (part "1825910-6"))
    )
    (comp (ref "SW2")
      (value "1825910-6")
      (footprint "1825910-6")
      (description "SWITCH TACTILE SPST-NO 0.05A 24V")
      (fields
        (field (name "MANUFACTURER") "TE Connectivity")
        (field (name ".CREATOR") "MM")
        (field (name ".CHECKED PCB") "RF")
        (field (name ".CHECKED SCH") "RF")
      )
      (libsource (lib "28Pins_Project_V1I1_PCB") (part "1825910-6"))
    )
    (comp (ref "U1")
      (value "ATMEGA328P-PU")
      (footprint "28_DIP_7.62mm")
      (description "IC MCU 8BIT 32KB FLASH 28DIP")
      (fields
        (field (name "MANUFACTURER") "Atmel")
        (field (name ".CREATOR") "MM")
        (field (name ".CHECKED PCB") "RF")
        (field (name ".CHECKED SCH") "RF")
      )
      (libsource (lib "28Pins_Project_V1I1_PCB") (part "ATMEGA328P-PU"))
    )
    (comp (ref "U2")
      (value "ATMEGA16U2-AU")
      (footprint "TQFP32")
      (description "IC MCU 8BIT 16KB FLASH 32TQFP")
      (fields
        (field (name "MANUFACTURER") "Atmel")
        (field (name ".CREATOR") "MM")
        (field (name ".CHECKED PCB") "RF")
        (field (name ".CHECKED SCH") "RF")
      )
      (libsource (lib "28Pins_Project_V1I1_PCB") (part "ATMEGA16U2-AU"))
    )
    (comp (ref "U3")
      (value "TL1963A-33DCQR")
      (footprint "DCQ (R-PDSO-G6)")
      (description "IC REG LDO 3.3V 1.5A SOT223-6")
      (fields
        (field (name "MANUFACTURER") "Texas Instruments")
        (field (name ".CREATOR") "MM")
        (field (name ".CHECKED PCB") "RF")
        (field (name ".CHECKED SCH") "RF")
      )
      (libsource (lib "28Pins_Project_V1I1_PCB") (part "TL1963A-33DCQR"))
    )
    (comp (ref "U4")
      (value "SN74AHC1G09DBVR")
      (footprint "DBV_SOT_23_5")
      (description "IC GATE AND SGL 2INP SOT23-5")
      (fields (field (name "MANUFACTURER") "Texas Instruments") (field (name ".CREATOR") "MM"))
      (libsource (lib "28Pins_Project_V1I1_PCB") (part "SN74AHC1G09DBVR"))
    )
    (comp (ref "U5")
      (value "SN74AHC1G09DBVR")
      (footprint "DBV_SOT_23_5")
      (description "IC GATE AND SGL 2INP SOT23-5")
      (fields (field (name "MANUFACTURER") "Texas Instruments") (field (name ".CREATOR") "MM"))
      (libsource (lib "28Pins_Project_V1I1_PCB") (part "SN74AHC1G09DBVR"))
    )
    (comp (ref "U6")
      (value "SN74AHC1G09DBVR")
      (footprint "DBV_SOT_23_5")
      (description "IC GATE AND SGL 2INP SOT23-5")
      (fields (field (name "MANUFACTURER") "Texas Instruments") (field (name ".CREATOR") "MM"))
      (libsource (lib "28Pins_Project_V1I1_PCB") (part "SN74AHC1G09DBVR"))
    )
    (comp (ref "U7")
      (value "SN74AHC1G09DBVR")
      (footprint "DBV_SOT_23_5")
      (description "IC GATE AND SGL 2INP SOT23-5")
      (fields (field (name "MANUFACTURER") "Texas Instruments") (field (name ".CREATOR") "MM"))
      (libsource (lib "28Pins_Project_V1I1_PCB") (part "SN74AHC1G09DBVR"))
    )
    (comp (ref "Y1")
      (value "ABM7-16.000MHZ-D2Y-T")
      (footprint "ABM7_v1_1_BIG")
      (description "CRYSTAL 16MHZ 18PF SMD")
      (fields
        (field (name "MANUFACTURER") "Abracon LLC")
        (field (name ".CREATOR") "MM")
        (field (name ".CHECKED PCB") "RF")
        (field (name ".CHECKED SCH") "RF")
      )
      (libsource (lib "28Pins_Project_V1I1_PCB") (part "ABM7-16.000MHZ-D2Y-T"))
    )
    (comp (ref "Y2")
      (value "ABM7-16.000MHZ-D2Y-T")
      (footprint "ABM7_v1_1_BIG")
      (description "CRYSTAL 16MHZ 18PF SMD")
      (fields
        (field (name "MANUFACTURER") "Abracon LLC")
        (field (name ".CREATOR") "MM")
        (field (name ".CHECKED PCB") "RF")
        (field (name ".CHECKED SCH") "RF")
      )
      (libsource (lib "28Pins_Project_V1I1_PCB") (part "ABM7-16.000MHZ-D2Y-T"))
    )
    (comp (ref "Z1")
      (value "CG0603MLC-05E")
      (footprint "R0603")
      (description "VARISTOR 0603")
      (fields
        (field (name "MANUFACTURER") "Bourns Inc.")
        (field (name ".CREATOR") "MM")
        (field (name ".CHECKED PCB") "RF")
        (field (name ".CHECKED SCH") "RF")
      )
      (libsource (lib "28Pins_Project_V1I1_PCB") (part "CG0603MLC-05E"))
    )
    (comp (ref "Z2")
      (value "CG0603MLC-05E")
      (footprint "R0603")
      (description "VARISTOR 0603")
      (fields
        (field (name "MANUFACTURER") "Bourns Inc.")
        (field (name ".CREATOR") "MM")
        (field (name ".CHECKED PCB") "RF")
        (field (name ".CHECKED SCH") "RF")
      )
      (libsource (lib "28Pins_Project_V1I1_PCB") (part "CG0603MLC-05E"))
    )
  )
  (nets
    (net (code "1") (name "+AREF") (class "Default")
      (node (ref "C21") (pin "1") (pinfunction "1_1") (pintype "passive"))
      (node (ref "C24") (pin "1") (pinfunction "1_1") (pintype "passive"))
      (node (ref "J4") (pin "8") (pinfunction "8_8") (pintype "passive"))
      (node (ref "U1") (pin "21") (pinfunction "AREF_21") (pintype "passive"))
    )
    (net (code "2") (name "/+3V3_16U2_UCAP") (class "Default")
      (node (ref "C7") (pin "2") (pinfunction "2_2") (pintype "passive"))
      (node (ref "R26") (pin "1") (pinfunction "1_1") (pintype "passive"))
      (node (ref "U2") (pin "27") (pinfunction "UCAP_27") (pintype "passive"))
    )
    (net (code "3") (name "/+5V_USB") (class "Default")
      (node (ref "C1") (pin "1") (pinfunction "1_1") (pintype "passive"))
      (node (ref "J7") (pin "1") (pinfunction "P1_1") (pintype "passive"))
      (node (ref "L1") (pin "1") (pinfunction "1_1") (pintype "passive"))
    )
    (net (code "4") (name "/+5V{slash}3V3_16U2") (class "Default")
      (node (ref "C3") (pin "1") (pinfunction "1_1") (pintype "passive"))
      (node (ref "C4") (pin "1") (pinfunction "1_1") (pintype "passive"))
      (node (ref "C5") (pin "1") (pinfunction "1_1") (pintype "passive"))
      (node (ref "FB1") (pin "2") (pinfunction "2_2") (pintype "passive"))
      (node (ref "R26") (pin "2") (pinfunction "2_2") (pintype "passive"))
      (node (ref "U2") (pin "32") (pinfunction "AVCC_32") (pintype "passive"))
      (node (ref "U2") (pin "4") (pinfunction "VCC_4") (pintype "passive"))
    )
    (net (code "5") (name "/+5V{slash}3V3_328P_AVCC") (class "Default")
      (node (ref "C22") (pin "1") (pinfunction "1_1") (pintype "passive"))
      (node (ref "C23") (pin "1") (pinfunction "1_1") (pintype "passive"))
      (node (ref "FB3") (pin "2") (pinfunction "2_2") (pintype "passive"))
      (node (ref "U1") (pin "20") (pinfunction "AVCC_20") (pintype "passive"))
    )
    (net (code "6") (name "/+5V{slash}3V3_328P_VCC") (class "Default")
      (node (ref "C19") (pin "1") (pinfunction "1_1") (pintype "passive"))
      (node (ref "C20") (pin "1") (pinfunction "1_1") (pintype "passive"))
      (node (ref "FB2") (pin "2") (pinfunction "2_2") (pintype "passive"))
      (node (ref "U1") (pin "7") (pinfunction "VCC_7") (pintype "passive"))
    )
    (net (code "7") (name "/16U2PROG_328P_RESETn") (class "Default")
      (node (ref "JP1") (pin "2") (pinfunction "2_2") (pintype "passive"))
      (node (ref "R1") (pin "1") (pinfunction "1_1") (pintype "passive"))
      (node (ref "U2") (pin "13") (pinfunction "(CTS/HWB/AIN6/TO/INT7)PD7_13") (pintype "passive"))
    )
    (net (code "8") (name "/16U2_16MHZ_XTAL1") (class "Default")
      (node (ref "C10") (pin "2") (pinfunction "2_2") (pintype "passive"))
      (node (ref "R9") (pin "1") (pinfunction "1_1") (pintype "passive"))
      (node (ref "U2") (pin "1") (pinfunction "XTAL1_1") (pintype "passive"))
      (node (ref "Y2") (pin "1") (pinfunction "1_1") (pintype "passive"))
    )
    (net (code "9") (name "/16U2_16MHZ_XTAL2") (class "Default")
      (node (ref "C9") (pin "2") (pinfunction "2_2") (pintype "passive"))
      (node (ref "R9") (pin "2") (pinfunction "2_2") (pintype "passive"))
      (node (ref "U2") (pin "2") (pinfunction "XTAL2(PC0)_2") (pintype "passive"))
      (node (ref "Y2") (pin "2") (pinfunction "2_2") (pintype "passive"))
    )
    (net (code "10") (name "/16U2_BUF_RESETn") (class "Default")
      (node (ref "C31") (pin "1") (pinfunction "1_1") (pintype "passive"))
      (node (ref "R23") (pin "2") (pinfunction "2_2") (pintype "passive"))
      (node (ref "U5") (pin "1") (pinfunction "A_1") (pintype "passive"))
      (node (ref "U5") (pin "2") (pinfunction "B_2") (pintype "passive"))
    )
    (net (code "11") (name "/16U2_HDR_RESETn") (class "Default")
      (node (ref "J6") (pin "5") (pinfunction "5_5") (pintype "passive"))
      (node (ref "JP3") (pin "3") (pinfunction "3_3") (pintype "passive"))
    )
    (net (code "12") (name "/16U2_MISO") (class "Default")
      (node (ref "J6") (pin "1") (pinfunction "1_1") (pintype "passive"))
      (node (ref "U2") (pin "17") (pinfunction "(PD0/MISO/PCINT3)PB3_17") (pintype "passive"))
    )
    (net (code "13") (name "/16U2_PB4") (class "Default")
      (node (ref "JP2") (pin "1") (pinfunction "1_1") (pintype "passive"))
      (node (ref "JP3") (pin "2") (pinfunction "2_2") (pintype "passive"))
      (node (ref "U2") (pin "18") (pinfunction "(T1/PCINT4)PB4_18") (pintype "passive"))
    )
    (net (code "14") (name "/16U2_PB5") (class "Default")
      (node (ref "JP2") (pin "3") (pinfunction "3_3") (pintype "passive"))
      (node (ref "U2") (pin "19") (pinfunction "(PCINT5)PB5_19") (pintype "passive"))
    )
    (net (code "15") (name "/16U2_PB6") (class "Default")
      (node (ref "JP2") (pin "2") (pinfunction "2_2") (pintype "passive"))
      (node (ref "U2") (pin "20") (pinfunction "(PCINT6)PB6_20") (pintype "passive"))
    )
    (net (code "16") (name "/16U2_PB7") (class "Default")
      (node (ref "JP2") (pin "4") (pinfunction "4_4") (pintype "passive"))
      (node (ref "U2") (pin "21") (pinfunction "(PCINT7/OC0A/OC1C)PB7_21") (pintype "passive"))
    )
    (net (code "17") (name "/16U2_RESETn") (class "Default")
      (node (ref "JP3") (pin "4") (pinfunction "4_4") (pintype "passive"))
      (node (ref "R4") (pin "1") (pinfunction "1_1") (pintype "passive"))
      (node (ref "U2") (pin "24") (pinfunction "RESET(PC1/DW)_24") (pintype "passive"))
      (node (ref "U5") (pin "4") (pinfunction "Y_4") (pintype "passive"))
    )
    (net (code "18") (name "/16U2_RXD") (class "Default")
      (node (ref "R11") (pin "1") (pinfunction "1_1") (pintype "passive"))
      (node (ref "U2") (pin "8") (pinfunction "(RXD1/AIN1/INT2)PD2_8") (pintype "passive"))
    )
    (net (code "19") (name "/16U2_RX_LED") (class "Default")
      (node (ref "D4") (pin "1") (pinfunction "cathode_1") (pintype "passive"))
      (node (ref "U2") (pin "10") (pinfunction "(INT5/AIN3)PD4_10") (pintype "passive"))
    )
    (net (code "20") (name "/16U2_SCLK") (class "Default")
      (node (ref "J6") (pin "3") (pinfunction "3_3") (pintype "passive"))
      (node (ref "R5") (pin "2") (pinfunction "2_2") (pintype "passive"))
    )
    (net (code "21") (name "/16U2_SCLK_R") (class "Default")
      (node (ref "R5") (pin "1") (pinfunction "1_1") (pintype "passive"))
      (node (ref "U2") (pin "15") (pinfunction "(SCLK/PCINT1)PB1_15") (pintype "passive"))
    )
    (net (code "22") (name "/16U2_TXD") (class "Default")
      (node (ref "R10") (pin "1") (pinfunction "1_1") (pintype "passive"))
      (node (ref "U2") (pin "9") (pinfunction "(TXD1/INT3)PD3_9") (pintype "passive"))
    )
    (net (code "23") (name "/16U2_TX_LED") (class "Default")
      (node (ref "D3") (pin "1") (pinfunction "cathode_1") (pintype "passive"))
      (node (ref "U2") (pin "11") (pinfunction "(XCK/AIN4/PCINT12)PD5_11") (pintype "passive"))
    )
    (net (code "24") (name "/328P_16MHZ_XTAL1") (class "Default")
      (node (ref "C27") (pin "2") (pinfunction "2_2") (pintype "passive"))
      (node (ref "R16") (pin "1") (pinfunction "1_1") (pintype "passive"))
      (node (ref "U1") (pin "9") (pinfunction "XTAL1_9") (pintype "passive"))
      (node (ref "Y1") (pin "1") (pinfunction "1_1") (pintype "passive"))
    )
    (net (code "25") (name "/328P_16MHZ_XTAL2") (class "Default")
      (node (ref "C25") (pin "2") (pinfunction "2_2") (pintype "passive"))
      (node (ref "R16") (pin "2") (pinfunction "2_2") (pintype "passive"))
      (node (ref "U1") (pin "10") (pinfunction "XTAL2_10") (pintype "passive"))
      (node (ref "Y1") (pin "2") (pinfunction "2_2") (pintype "passive"))
    )
    (net (code "26") (name "/328P_AUTORESETn") (class "Default")
      (node (ref "C11") (pin "1") (pinfunction "1_1") (pintype "passive"))
      (node (ref "R18") (pin "1") (pinfunction "1_1") (pintype "passive"))
      (node (ref "U6") (pin "1") (pinfunction "A_1") (pintype "passive"))
    )
    (net (code "27") (name "/328P_BUF_RESETn") (class "Default")
      (node (ref "C32") (pin "1") (pinfunction "1_1") (pintype "passive"))
      (node (ref "R24") (pin "2") (pinfunction "2_2") (pintype "passive"))
      (node (ref "U6") (pin "2") (pinfunction "B_2") (pintype "passive"))
    )
    (net (code "28") (name "/328P_RESETn") (class "Default")
      (node (ref "J1") (pin "3") (pinfunction "3_3") (pintype "passive"))
      (node (ref "J5") (pin "5") (pinfunction "5_5") (pintype "passive"))
      (node (ref "JP3") (pin "1") (pinfunction "1_1") (pintype "passive"))
      (node (ref "R14") (pin "1") (pinfunction "1_1") (pintype "passive"))
      (node (ref "U1") (pin "1") (pinfunction "RESET_1") (pintype "passive"))
      (node (ref "U6") (pin "4") (pinfunction "Y_4") (pintype "passive"))
    )
    (net (code "29") (name "/AD0") (class "Default")
      (node (ref "J2") (pin "1") (pinfunction "1_1") (pintype "passive"))
      (node (ref "U1") (pin "23") (pinfunction "(ADC0)PC0)_23") (pintype "passive"))
    )
    (net (code "30") (name "/AD1") (class "Default")
      (node (ref "J2") (pin "2") (pinfunction "2_2") (pintype "passive"))
      (node (ref "U1") (pin "24") (pinfunction "(ADC1)PC1_24") (pintype "passive"))
    )
    (net (code "31") (name "/AD2") (class "Default")
      (node (ref "J2") (pin "3") (pinfunction "3_3") (pintype "passive"))
      (node (ref "U1") (pin "25") (pinfunction "(ADC2)PC2_25") (pintype "passive"))
    )
    (net (code "32") (name "/AD3") (class "Default")
      (node (ref "J2") (pin "4") (pinfunction "4_4") (pintype "passive"))
      (node (ref "U1") (pin "26") (pinfunction "(ADC3)PC3_26") (pintype "passive"))
    )
    (net (code "33") (name "/AD4{slash}SDA") (class "Default")
      (node (ref "J2") (pin "5") (pinfunction "5_5") (pintype "passive"))
      (node (ref "J4") (pin "9") (pinfunction "9_9") (pintype "passive"))
      (node (ref "U1") (pin "27") (pinfunction "(ADC4)PC4_27") (pintype "passive"))
    )
    (net (code "34") (name "/AD5{slash}SCL") (class "Default")
      (node (ref "J2") (pin "6") (pinfunction "6_6") (pintype "passive"))
      (node (ref "J4") (pin "10") (pinfunction "10_10") (pintype "passive"))
      (node (ref "U1") (pin "28") (pinfunction "(ADC5)PC5_28") (pintype "passive"))
    )
    (net (code "35") (name "/BUTTON_RESETn") (class "Default")
      (node (ref "D6") (pin "2") (pinfunction "Anode_2") (pintype "passive"))
      (node (ref "R20") (pin "1") (pinfunction "1_1") (pintype "passive"))
      (node (ref "R24") (pin "1") (pinfunction "1_1") (pintype "passive"))
      (node (ref "SW1") (pin "1") (pinfunction "1_1") (pintype "passive"))
      (node (ref "SW1") (pin "2") (pinfunction "2_2") (pintype "passive"))
    )
    (net (code "36") (name "/CON_USB_N") (class "Default")
      (node (ref "J7") (pin "2") (pinfunction "P2_2") (pintype "passive"))
      (node (ref "R6") (pin "1") (pinfunction "1_1") (pintype "passive"))
      (node (ref "Z1") (pin "2") (pinfunction "2_2") (pintype "passive"))
    )
    (net (code "37") (name "/CON_USB_P") (class "Default")
      (node (ref "J7") (pin "3") (pinfunction "P3_3") (pintype "passive"))
      (node (ref "R7") (pin "1") (pinfunction "1_1") (pintype "passive"))
      (node (ref "Z2") (pin "2") (pinfunction "2_2") (pintype "passive"))
    )
    (net (code "38") (name "/IO0") (class "Default")
      (node (ref "J3") (pin "1") (pinfunction "1_1") (pintype "passive"))
      (node (ref "R10") (pin "2") (pinfunction "2_2") (pintype "passive"))
      (node (ref "U1") (pin "2") (pinfunction "(RXD)PD0_2") (pintype "passive"))
    )
    (net (code "39") (name "/IO1") (class "Default")
      (node (ref "J3") (pin "2") (pinfunction "2_2") (pintype "passive"))
      (node (ref "R11") (pin "2") (pinfunction "2_2") (pintype "passive"))
      (node (ref "U1") (pin "3") (pinfunction "(TXD)PD1_3") (pintype "passive"))
    )
    (net (code "40") (name "/IO2") (class "Default")
      (node (ref "J3") (pin "3") (pinfunction "3_3") (pintype "passive"))
      (node (ref "U1") (pin "4") (pinfunction "(INT0)PD2_4") (pintype "passive"))
    )
    (net (code "41") (name "/IO3") (class "Default")
      (node (ref "J3") (pin "4") (pinfunction "4_4") (pintype "passive"))
      (node (ref "U1") (pin "5") (pinfunction "(INT1)PD3_5") (pintype "passive"))
    )
    (net (code "42") (name "/IO4") (class "Default")
      (node (ref "J3") (pin "5") (pinfunction "5_5") (pintype "passive"))
      (node (ref "U1") (pin "6") (pinfunction "(T0)PD4_6") (pintype "passive"))
    )
    (net (code "43") (name "/IO5") (class "Default")
      (node (ref "J3") (pin "6") (pinfunction "6_6") (pintype "passive"))
      (node (ref "U1") (pin "11") (pinfunction "(T1)PD5_11") (pintype "passive"))
    )
    (net (code "44") (name "/IO6") (class "Default")
      (node (ref "J3") (pin "7") (pinfunction "7_7") (pintype "passive"))
      (node (ref "U1") (pin "12") (pinfunction "(AIN0)PD6_12") (pintype "passive"))
    )
    (net (code "45") (name "/IO7") (class "Default")
      (node (ref "J3") (pin "8") (pinfunction "8_8") (pintype "passive"))
      (node (ref "U1") (pin "13") (pinfunction "(AIN1)PD7_13") (pintype "passive"))
    )
    (net (code "46") (name "/IO8") (class "Default")
      (node (ref "J4") (pin "1") (pinfunction "1_1") (pintype "passive"))
      (node (ref "R22") (pin "1") (pinfunction "1_1") (pintype "passive"))
      (node (ref "U1") (pin "14") (pinfunction "(ICP)PB0_14") (pintype "passive"))
    )
    (net (code "47") (name "/IO9") (class "Default")
      (node (ref "J4") (pin "2") (pinfunction "2_2") (pintype "passive"))
      (node (ref "U1") (pin "15") (pinfunction "(OC1)PB1_15") (pintype "passive"))
    )
    (net (code "48") (name "/MISO") (class "Default")
      (node (ref "J4") (pin "5") (pinfunction "5_5") (pintype "passive"))
      (node (ref "J5") (pin "1") (pinfunction "1_1") (pintype "passive"))
      (node (ref "U1") (pin "18") (pinfunction "(MISO)PB4_18") (pintype "passive"))
    )
    (net (code "49") (name "/MOSI") (class "Default")
      (node (ref "J4") (pin "4") (pinfunction "4_4") (pintype "passive"))
      (node (ref "J5") (pin "4") (pinfunction "4_4") (pintype "passive"))
      (node (ref "U1") (pin "17") (pinfunction "(MOSI)PB3_17") (pintype "passive"))
    )
    (net (code "50") (name "/SCK") (class "Default")
      (node (ref "J4") (pin "6") (pinfunction "6_6") (pintype "passive"))
      (node (ref "J5") (pin "3") (pinfunction "3_3") (pintype "passive"))
      (node (ref "R13") (pin "2") (pinfunction "2_2") (pintype "passive"))
      (node (ref "U4") (pin "1") (pinfunction "A_1") (pintype "passive"))
      (node (ref "U4") (pin "2") (pinfunction "B_2") (pintype "passive"))
    )
    (net (code "51") (name "/SCK_R") (class "Default")
      (node (ref "R13") (pin "1") (pinfunction "1_1") (pintype "passive"))
      (node (ref "U1") (pin "19") (pinfunction "(SCK)PB5_19") (pintype "passive"))
    )
    (net (code "52") (name "/SS") (class "Default")
      (node (ref "J4") (pin "3") (pinfunction "3_3") (pintype "passive"))
      (node (ref "U1") (pin "16") (pinfunction "(SS)PB2_16") (pintype "passive"))
    )
    (net (code "53") (name "/USB_N") (class "Default")
      (node (ref "R6") (pin "2") (pinfunction "2_2") (pintype "passive"))
      (node (ref "U2") (pin "30") (pinfunction "D-_30") (pintype "passive"))
    )
    (net (code "54") (name "/USB_P") (class "Default")
      (node (ref "R7") (pin "2") (pinfunction "2_2") (pintype "passive"))
      (node (ref "U2") (pin "29") (pinfunction "D+_29") (pintype "passive"))
    )
    (net (code "55") (name "/USER_BUTTON") (class "Default")
      (node (ref "R21") (pin "1") (pinfunction "1_1") (pintype "passive"))
      (node (ref "R25") (pin "1") (pinfunction "1_1") (pintype "passive"))
      (node (ref "SW2") (pin "1") (pinfunction "1_1") (pintype "passive"))
      (node (ref "SW2") (pin "2") (pinfunction "2_2") (pintype "passive"))
    )
    (net (code "56") (name "/USER_BUTTON_BUF") (class "Default")
      (node (ref "C33") (pin "1") (pinfunction "1_1") (pintype "passive"))
      (node (ref "R25") (pin "2") (pinfunction "2_2") (pintype "passive"))
      (node (ref "U7") (pin "1") (pinfunction "A_1") (pintype "passive"))
      (node (ref "U7") (pin "2") (pinfunction "B_2") (pintype "passive"))
    )
    (net (code "57") (name "3V3") (class "Default")
      (node (ref "C13") (pin "1") (pinfunction "1_1") (pintype "passive"))
      (node (ref "C16") (pin "1") (pinfunction "1_1") (pintype "passive"))
      (node (ref "J1") (pin "4") (pinfunction "4_4") (pintype "passive"))
      (node (ref "JP4") (pin "3") (pinfunction "3_3") (pintype "passive"))
      (node (ref "R28") (pin "1") (pinfunction "1_1") (pintype "passive"))
      (node (ref "U3") (pin "4") (pinfunction "OUT_4") (pintype "passive"))
    )
    (net (code "58") (name "5V0") (class "Default")
      (node (ref "C12") (pin "1") (pinfunction "1_1") (pintype "passive"))
      (node (ref "C14") (pin "1") (pinfunction "1_1") (pintype "passive"))
      (node (ref "C2") (pin "1") (pinfunction "1_1") (pintype "passive"))
      (node (ref "C6") (pin "1") (pinfunction "1_1") (pintype "passive"))
      (node (ref "J1") (pin "5") (pinfunction "5_5") (pintype "passive"))
      (node (ref "J8") (pin "1") (pinfunction "1_1") (pintype "passive"))
      (node (ref "JP4") (pin "1") (pinfunction "1_1") (pintype "passive"))
      (node (ref "L1") (pin "2") (pinfunction "2_2") (pintype "passive"))
      (node (ref "R27") (pin "2") (pinfunction "2_2") (pintype "passive"))
      (node (ref "U2") (pin "31") (pinfunction "UVCC_31") (pintype "passive"))
      (node (ref "U3") (pin "1") (pinfunction "~{SHDN}_1") (pintype "passive"))
      (node (ref "U3") (pin "2") (pinfunction "IN_2") (pintype "passive"))
    )
    (net (code "59") (name "5V0{slash}3V3") (class "Default")
      (node (ref "C15") (pin "1") (pinfunction "1_1") (pintype "passive"))
      (node (ref "C17") (pin "1") (pinfunction "1_1") (pintype "passive"))
      (node (ref "C26") (pin "1") (pinfunction "1_1") (pintype "passive"))
      (node (ref "C28") (pin "1") (pinfunction "1_1") (pintype "passive"))
      (node (ref "C29") (pin "1") (pinfunction "1_1") (pintype "passive"))
      (node (ref "C30") (pin "1") (pinfunction "1_1") (pintype "passive"))
      (node (ref "C34") (pin "1") (pinfunction "1_1") (pintype "passive"))
      (node (ref "C8") (pin "1") (pinfunction "1_1") (pintype "passive"))
      (node (ref "D5") (pin "1") (pinfunction "Cathode_1") (pintype "passive"))
      (node (ref "D6") (pin "1") (pinfunction "Cathode_1") (pintype "passive"))
      (node (ref "FB1") (pin "1") (pinfunction "1_1") (pintype "passive"))
      (node (ref "FB2") (pin "1") (pinfunction "1_1") (pintype "passive"))
      (node (ref "FB3") (pin "1") (pinfunction "1_1") (pintype "passive"))
      (node (ref "J1") (pin "2") (pinfunction "2_2") (pintype "passive"))
      (node (ref "J5") (pin "2") (pinfunction "2_2") (pintype "passive"))
      (node (ref "J6") (pin "2") (pinfunction "2_2") (pintype "passive"))
      (node (ref "J6") (pin "4") (pinfunction "4_4") (pintype "passive"))
      (node (ref "JP4") (pin "2") (pinfunction "2_2") (pintype "passive"))
      (node (ref "R1") (pin "2") (pinfunction "2_2") (pintype "passive"))
      (node (ref "R14") (pin "2") (pinfunction "2_2") (pintype "passive"))
      (node (ref "R15") (pin "2") (pinfunction "2_2") (pintype "passive"))
      (node (ref "R17") (pin "2") (pinfunction "2_2") (pintype "passive"))
      (node (ref "R18") (pin "2") (pinfunction "2_2") (pintype "passive"))
      (node (ref "R19") (pin "2") (pinfunction "2_2") (pintype "passive"))
      (node (ref "R2") (pin "2") (pinfunction "2_2") (pintype "passive"))
      (node (ref "R20") (pin "2") (pinfunction "2_2") (pintype "passive"))
      (node (ref "R21") (pin "2") (pinfunction "2_2") (pintype "passive"))
      (node (ref "R27") (pin "1") (pinfunction "1_1") (pintype "passive"))
      (node (ref "R28") (pin "2") (pinfunction "2_2") (pintype "passive"))
      (node (ref "R3") (pin "2") (pinfunction "2_2") (pintype "passive"))
      (node (ref "R4") (pin "2") (pinfunction "2_2") (pintype "passive"))
      (node (ref "U2") (pin "16") (pinfunction "(PDI/MOSI/PCINT2)PB2_16") (pintype "passive"))
      (node (ref "U4") (pin "5") (pinfunction "VCC_5") (pintype "power_in"))
      (node (ref "U5") (pin "5") (pinfunction "VCC_5") (pintype "power_in"))
      (node (ref "U6") (pin "5") (pinfunction "VCC_5") (pintype "power_in"))
      (node (ref "U7") (pin "5") (pinfunction "VCC_5") (pintype "power_in"))
    )
    (net (code "60") (name "GND") (class "Default")
      (node (ref "C1") (pin "2") (pinfunction "2_2") (pintype "passive"))
      (node (ref "C10") (pin "1") (pinfunction "1_1") (pintype "passive"))
      (node (ref "C12") (pin "2") (pinfunction "2_2") (pintype "passive"))
      (node (ref "C13") (pin "2") (pinfunction "2_2") (pintype "passive"))
      (node (ref "C14") (pin "2") (pinfunction "2_2") (pintype "passive"))
      (node (ref "C15") (pin "2") (pinfunction "2_2") (pintype "passive"))
      (node (ref "C16") (pin "2") (pinfunction "2_2") (pintype "passive"))
      (node (ref "C17") (pin "2") (pinfunction "2_2") (pintype "passive"))
      (node (ref "C19") (pin "2") (pinfunction "2_2") (pintype "passive"))
      (node (ref "C2") (pin "2") (pinfunction "2_2") (pintype "passive"))
      (node (ref "C20") (pin "2") (pinfunction "2_2") (pintype "passive"))
      (node (ref "C21") (pin "2") (pinfunction "2_2") (pintype "passive"))
      (node (ref "C22") (pin "2") (pinfunction "2_2") (pintype "passive"))
      (node (ref "C23") (pin "2") (pinfunction "2_2") (pintype "passive"))
      (node (ref "C24") (pin "2") (pinfunction "2_2") (pintype "passive"))
      (node (ref "C25") (pin "1") (pinfunction "1_1") (pintype "passive"))
      (node (ref "C26") (pin "2") (pinfunction "2_2") (pintype "passive"))
      (node (ref "C27") (pin "1") (pinfunction "1_1") (pintype "passive"))
      (node (ref "C28") (pin "2") (pinfunction "2_2") (pintype "passive"))
      (node (ref "C29") (pin "2") (pinfunction "2_2") (pintype "passive"))
      (node (ref "C3") (pin "2") (pinfunction "2_2") (pintype "passive"))
      (node (ref "C30") (pin "2") (pinfunction "2_2") (pintype "passive"))
      (node (ref "C31") (pin "2") (pinfunction "2_2") (pintype "passive"))
      (node (ref "C32") (pin "2") (pinfunction "2_2") (pintype "passive"))
      (node (ref "C33") (pin "2") (pinfunction "2_2") (pintype "passive"))
      (node (ref "C34") (pin "2") (pinfunction "2_2") (pintype "passive"))
      (node (ref "C4") (pin "2") (pinfunction "2_2") (pintype "passive"))
      (node (ref "C5") (pin "2") (pinfunction "2_2") (pintype "passive"))
      (node (ref "C6") (pin "2") (pinfunction "2_2") (pintype "passive"))
      (node (ref "C7") (pin "1") (pinfunction "1_1") (pintype "passive"))
      (node (ref "C8") (pin "2") (pinfunction "2_2") (pintype "passive"))
      (node (ref "C9") (pin "1") (pinfunction "1_1") (pintype "passive"))
      (node (ref "D1") (pin "1") (pinfunction "cathode_1") (pintype "passive"))
      (node (ref "J1") (pin "6") (pinfunction "6_6") (pintype "passive"))
      (node (ref "J1") (pin "7") (pinfunction "7_7") (pintype "passive"))
      (node (ref "J4") (pin "7") (pinfunction "7_7") (pintype "passive"))
      (node (ref "J5") (pin "6") (pinfunction "6_6") (pintype "passive"))
      (node (ref "J6") (pin "6") (pinfunction "6_6") (pintype "passive"))
      (node (ref "J7") (pin "10") (pinfunction "10_10") (pintype "passive"))
      (node (ref "J7") (pin "11") (pinfunction "11_11") (pintype "passive"))
      (node (ref "J7") (pin "5") (pinfunction "P5_5") (pintype "passive"))
      (node (ref "J7") (pin "6") (pinfunction "6_6") (pintype "passive"))
      (node (ref "J7") (pin "7") (pinfunction "7_7") (pintype "passive"))
      (node (ref "J7") (pin "8") (pinfunction "8_8") (pintype "passive"))
      (node (ref "J7") (pin "9") (pinfunction "9_9") (pintype "passive"))
      (node (ref "J9") (pin "1") (pinfunction "1_1") (pintype "passive"))
      (node (ref "MH1") (pin "1") (pinfunction "1_1") (pintype "passive"))
      (node (ref "MH2") (pin "1") (pinfunction "1_1") (pintype "passive"))
      (node (ref "MH3") (pin "1") (pinfunction "1_1") (pintype "passive"))
      (node (ref "R12") (pin "2") (pinfunction "2_2") (pintype "passive"))
      (node (ref "R8") (pin "2") (pinfunction "2_2") (pintype "passive"))
      (node (ref "SW1") (pin "3") (pinfunction "MECH1_3") (pintype "passive"))
      (node (ref "SW1") (pin "4") (pinfunction "MECH2_4") (pintype "passive"))
      (node (ref "SW2") (pin "3") (pinfunction "MECH1_3") (pintype "passive"))
      (node (ref "SW2") (pin "4") (pinfunction "MECH2_4") (pintype "passive"))
      (node (ref "U1") (pin "22") (pinfunction "AGND_22") (pintype "passive"))
      (node (ref "U1") (pin "8") (pinfunction "GND_8") (pintype "passive"))
      (node (ref "U2") (pin "28") (pinfunction "UGND_28") (pintype "passive"))
      (node (ref "U2") (pin "3") (pinfunction "GND_3") (pintype "passive"))
      (node (ref "U3") (pin "3") (pinfunction "GND_3") (pintype "passive"))
      (node (ref "U3") (pin "6") (pinfunction "EPAD_6") (pintype "passive"))
      (node (ref "U4") (pin "3") (pinfunction "GND_3") (pintype "power_in"))
      (node (ref "U5") (pin "3") (pinfunction "GND_3") (pintype "power_in"))
      (node (ref "U6") (pin "3") (pinfunction "GND_3") (pintype "power_in"))
      (node (ref "U7") (pin "3") (pinfunction "GND_3") (pintype "power_in"))
      (node (ref "Z1") (pin "1") (pinfunction "1_1") (pintype "passive"))
      (node (ref "Z2") (pin "1") (pinfunction "1_1") (pintype "passive"))
    )
    (net (code "61") (name "Net-(C11-Pad2)") (class "Default")
      (node (ref "C11") (pin "2") (pinfunction "2_2") (pintype "passive"))
      (node (ref "JP1") (pin "1") (pinfunction "1_1") (pintype "passive"))
    )
    (net (code "62") (name "Net-(D1-ANODE)") (class "Default")
      (node (ref "D1") (pin "2") (pinfunction "ANODE_2") (pintype "passive"))
      (node (ref "R17") (pin "1") (pinfunction "1_1") (pintype "passive"))
    )
    (net (code "63") (name "Net-(D2-ANODE)") (class "Default")
      (node (ref "D2") (pin "2") (pinfunction "ANODE_2") (pintype "passive"))
      (node (ref "R15") (pin "1") (pinfunction "1_1") (pintype "passive"))
    )
    (net (code "64") (name "Net-(D2-cathode)") (class "Default")
      (node (ref "D2") (pin "1") (pinfunction "cathode_1") (pintype "passive"))
      (node (ref "U4") (pin "4") (pinfunction "Y_4") (pintype "passive"))
    )
    (net (code "65") (name "Net-(D3-ANODE)") (class "Default")
      (node (ref "D3") (pin "2") (pinfunction "ANODE_2") (pintype "passive"))
      (node (ref "R2") (pin "1") (pinfunction "1_1") (pintype "passive"))
    )
    (net (code "66") (name "Net-(D4-ANODE)") (class "Default")
      (node (ref "D4") (pin "2") (pinfunction "ANODE_2") (pintype "passive"))
      (node (ref "R3") (pin "1") (pinfunction "1_1") (pintype "passive"))
    )
    (net (code "67") (name "Net-(D5-Anode)") (class "Default")
      (node (ref "D5") (pin "2") (pinfunction "Anode_2") (pintype "passive"))
      (node (ref "R19") (pin "1") (pinfunction "1_1") (pintype "passive"))
      (node (ref "R23") (pin "1") (pinfunction "1_1") (pintype "passive"))
    )
    (net (code "68") (name "Net-(J7-P4)") (class "Default")
      (node (ref "J7") (pin "4") (pinfunction "P4_4") (pintype "passive"))
      (node (ref "R8") (pin "1") (pinfunction "1_1") (pintype "passive"))
    )
    (net (code "69") (name "Net-(JP1-Pad3)") (class "Default")
      (node (ref "JP1") (pin "3") (pinfunction "3_3") (pintype "passive"))
      (node (ref "R12") (pin "1") (pinfunction "1_1") (pintype "passive"))
    )
    (net (code "70") (name "Net-(U7-Y)") (class "Default")
      (node (ref "R22") (pin "2") (pinfunction "2_2") (pintype "passive"))
      (node (ref "U7") (pin "4") (pinfunction "Y_4") (pintype "passive"))
    )
    (net (code "71") (name "unconnected-(J1-Pad1)") (class "Default")
      (node (ref "J1") (pin "1") (pinfunction "1_1") (pintype "passive+no_connect"))
    )
    (net (code "72") (name "unconnected-(J1-Pad8)") (class "Default")
      (node (ref "J1") (pin "8") (pinfunction "8_8") (pintype "passive+no_connect"))
    )
    (net (code "73") (name "unconnected-(MH4-Pad1)") (class "Default")
      (node (ref "MH4") (pin "1") (pinfunction "1_1") (pintype "passive+no_connect"))
    )
    (net (code "74") (name "unconnected-(U2-(AIN0{slash}INT1)PD1-Pad7)") (class "Default")
      (node (ref "U2") (pin "7") (pinfunction "(AIN0/INT1)PD1_7") (pintype "passive+no_connect"))
    )
    (net (code "75") (name "unconnected-(U2-(AIN2{slash}PCINT11)PC2-Pad5)") (class "Default")
      (node (ref "U2") (pin "5") (pinfunction "(AIN2/PCINT11)PC2_5") (pintype "passive+no_connect"))
    )
    (net (code "76") (name "unconnected-(U2-(INT4{slash}ICP1{slash}CLK0)PC7-Pad22)") (class "Default")
      (node (ref "U2") (pin "22") (pinfunction "(INT4/ICP1/CLK0)PC7_22") (pintype "passive+no_connect"))
    )
    (net (code "77") (name "unconnected-(U2-(OC0B{slash}INT0)PD0-Pad6)") (class "Default")
      (node (ref "U2") (pin "6") (pinfunction "(OC0B/INT0)PD0_6") (pintype "passive+no_connect"))
    )
    (net (code "78") (name "unconnected-(U2-(OC1A{slash}PCINT8)PC6-Pad23)") (class "Default")
      (node (ref "U2") (pin "23") (pinfunction "(OC1A/PCINT8)PC6_23") (pintype "passive+no_connect"))
    )
    (net (code "79") (name "unconnected-(U2-(PCINT9{slash}OC1B)PC5-Pad25)") (class "Default")
      (node (ref "U2") (pin "25") (pinfunction "(PCINT9/OC1B)PC5_25") (pintype "passive+no_connect"))
    )
    (net (code "80") (name "unconnected-(U2-(PCINT10)PC4-Pad26)") (class "Default")
      (node (ref "U2") (pin "26") (pinfunction "(PCINT10)PC4_26") (pintype "passive+no_connect"))
    )
    (net (code "81") (name "unconnected-(U2-(RTS{slash}AIN5{slash}INT6)PD6-Pad12)") (class "Default")
      (node (ref "U2") (pin "12") (pinfunction "(RTS/AIN5/INT6)PD6_12") (pintype "passive"))
    )
    (net (code "82") (name "unconnected-(U2-(SS{slash}PCINT0)PB0-Pad14)") (class "Default")
      (node (ref "U2") (pin "14") (pinfunction "(SS/PCINT0)PB0_14") (pintype "passive+no_connect"))
    )
    (net (code "83") (name "unconnected-(U3-SENSE-Pad5)") (class "Default")
      (node (ref "U3") (pin "5") (pinfunction "SENSE_5") (pintype "passive"))
    )
  )
)
